# Motherboard.net
KiCad netlist of a schematic drawn in EAGLE
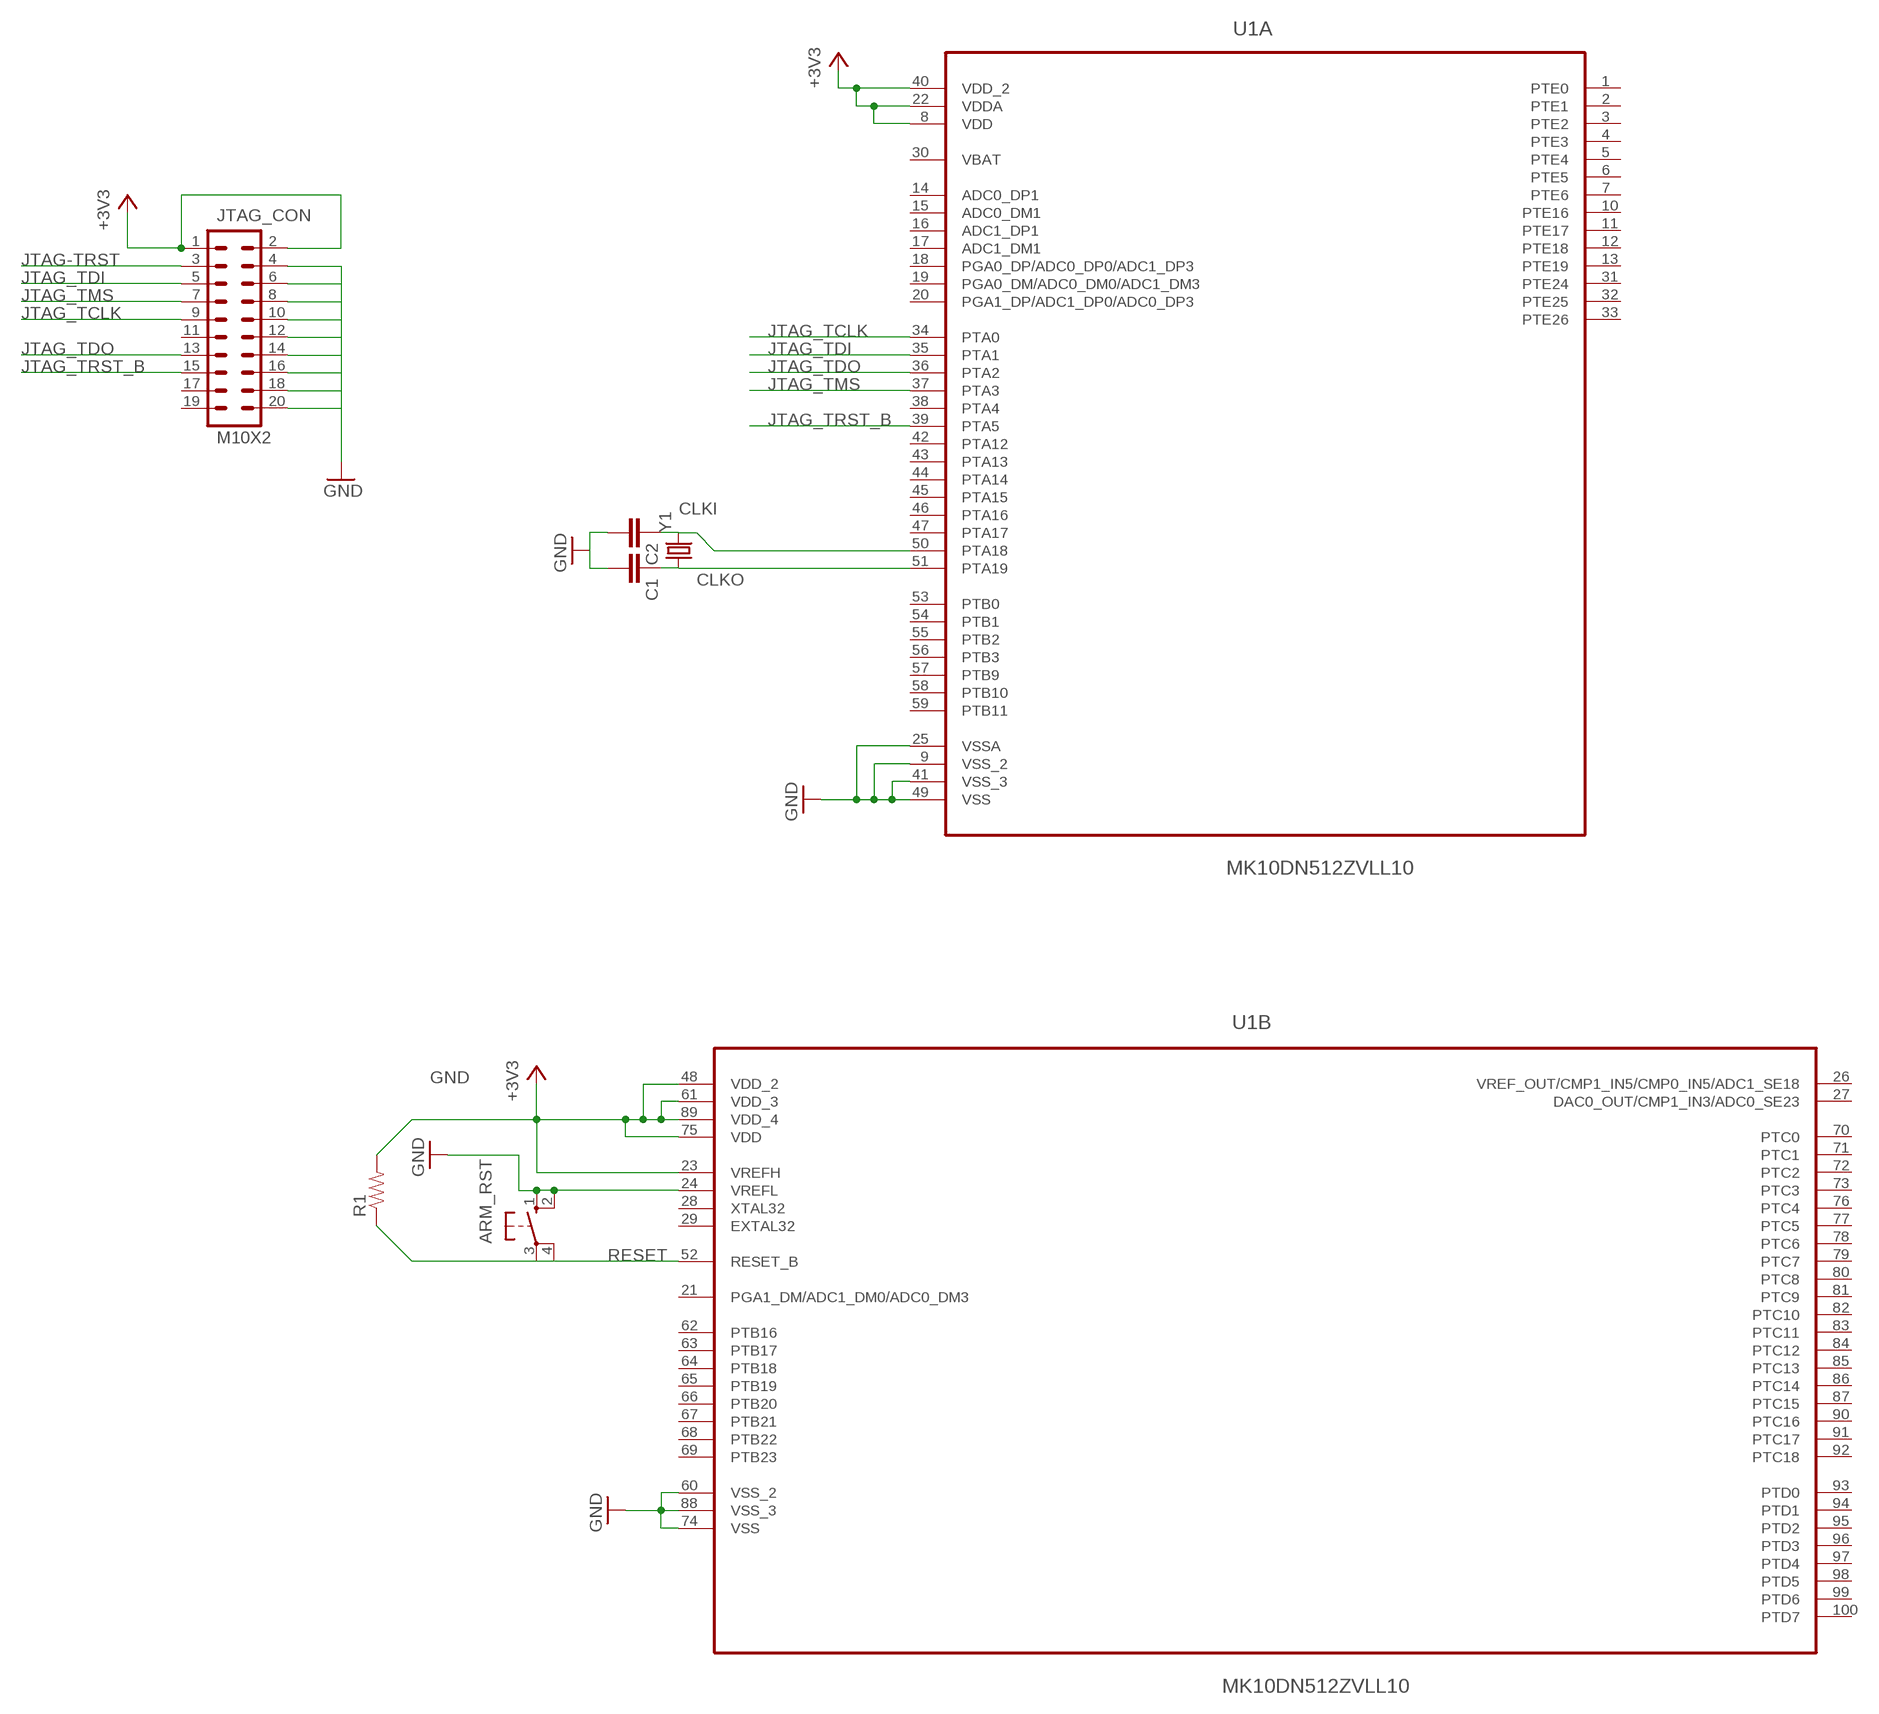
[diagram p0: schematic, sheet 1]
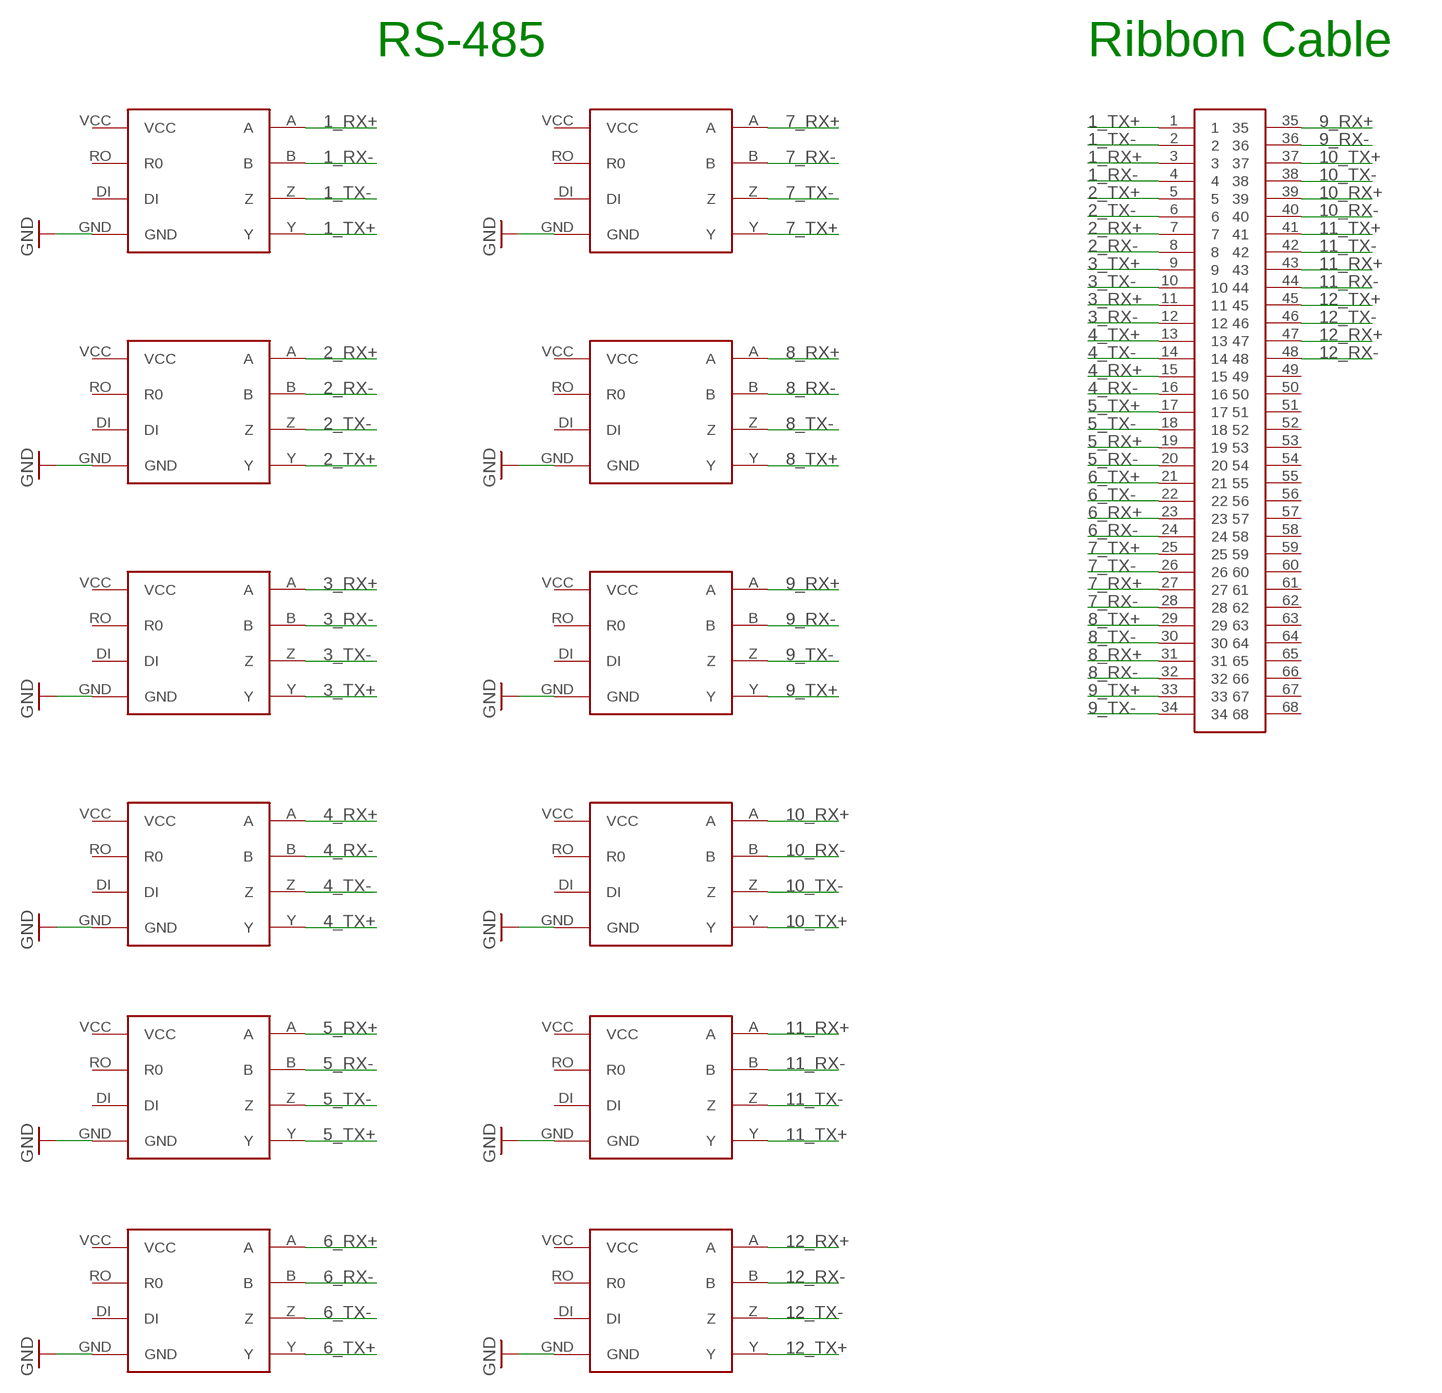
[diagram p1: schematic, sheet 2]
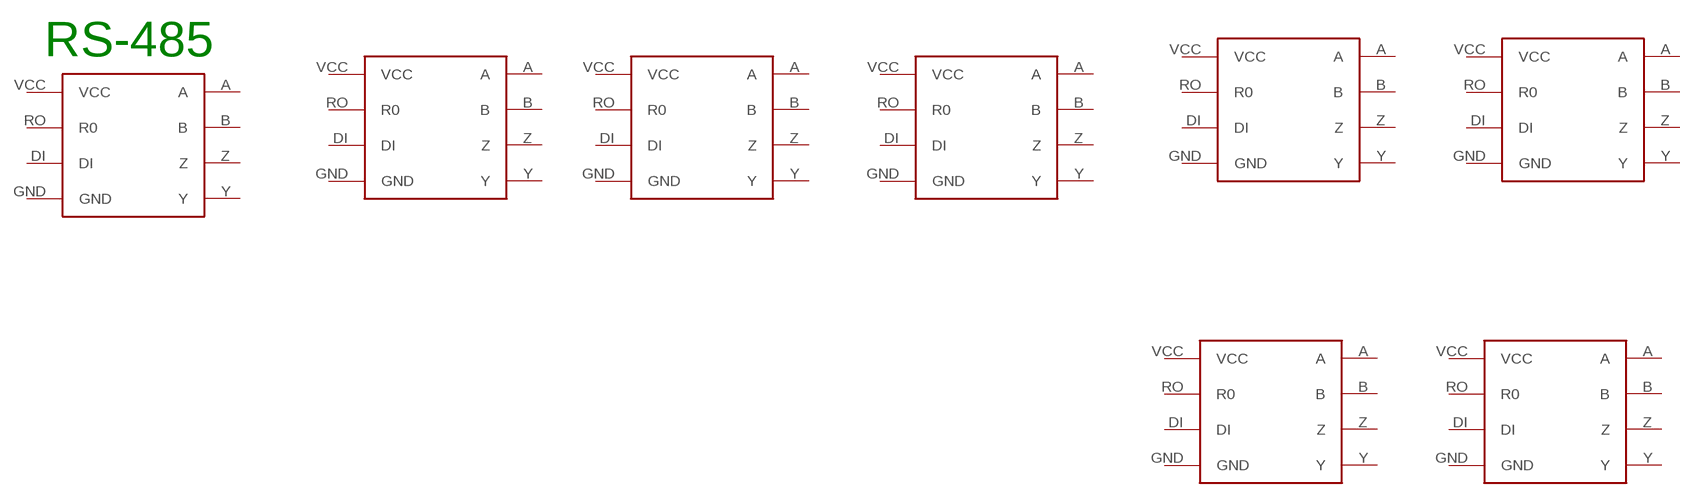
[diagram p2: schematic, sheet 3]
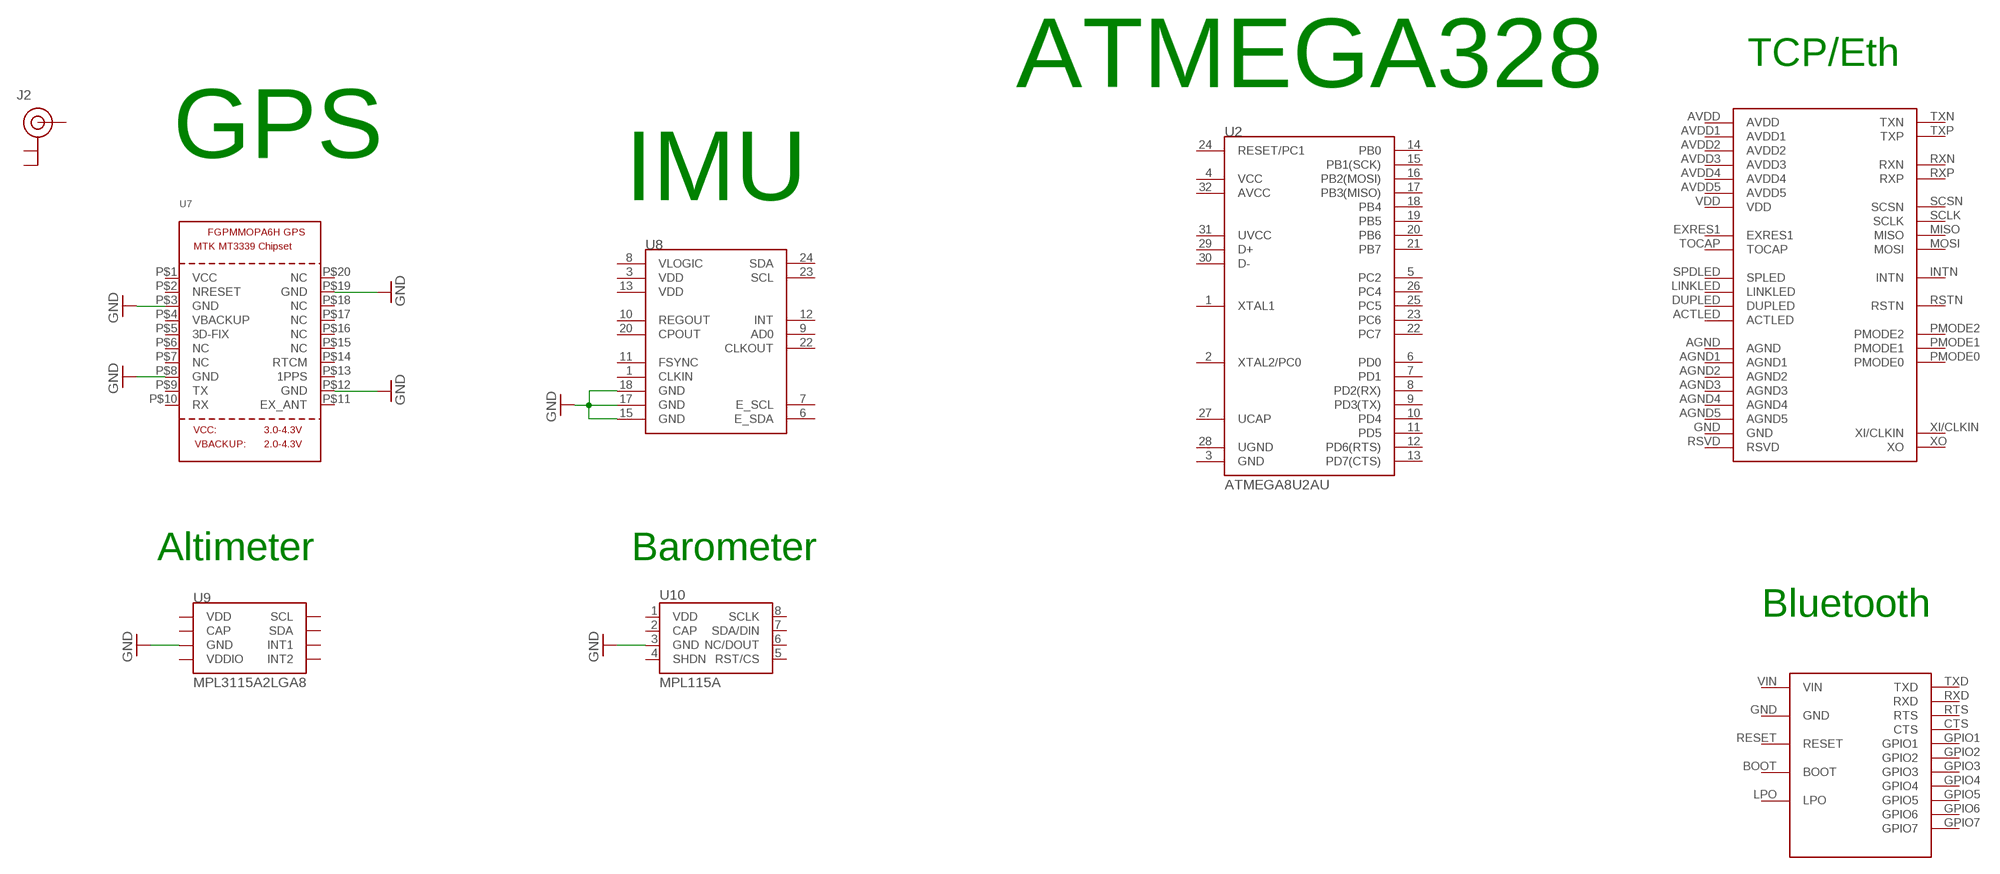
[diagram p3: schematic, sheet 4]

(export (version "E")
  (design (tool "Eeschema 10.0.6"))
  (components
    (comp (ref "ARM_RST")
      (value "10-XX")
      (footprint "eagle-import:B3F-10XX")
      (fields (field (name "MPN") "B3F-1000"))
      (libsource (lib "eagle-import") (part "10-XX"))
    )
    (comp (ref "C1")
      (value "CAPPTH1")
      (footprint "eagle-import:CAP-PTH-5MM")
      (libsource (lib "eagle-import") (part "CAPPTH1"))
    )
    (comp (ref "C2")
      (value "CAPPTH1")
      (footprint "eagle-import:CAP-PTH-5MM")
      (libsource (lib "eagle-import") (part "CAPPTH1"))
    )
    (comp (ref "JTAG_CON")
      (value "M10X2")
      (footprint "eagle-import:2X10")
      (libsource (lib "eagle-import") (part "M10X2"))
    )
    (comp (ref "R1")
      (value "RESISTORPTH-1/4W")
      (footprint "eagle-import:AXIAL-0.4")
      (libsource (lib "eagle-import") (part "RESISTORPTH-1/4W"))
    )
    (comp (ref "U1")
      (value "MK10DN512ZVLL10")
      (footprint "eagle-import:QFP50P1600X1600X170-100N")
      (libsource (lib "eagle-import") (part "MK10DN512ZVLL10"))
    )
    (comp (ref "Y1")
      (value "CRYSTALHC49US")
      (footprint "eagle-import:HC49US")
      (libsource (lib "eagle-import") (part "CRYSTALHC49US"))
    )
    (comp (ref "U$4")
      (value "MAX3077")
      (footprint "eagle-import:MAX3070E")
      (libsource (lib "eagle-import") (part "MAX3077"))
    )
    (comp (ref "U$25")
      (value "MAX3077")
      (footprint "eagle-import:MAX3070E")
      (libsource (lib "eagle-import") (part "MAX3077"))
    )
    (comp (ref "U$26")
      (value "MAX3077")
      (footprint "eagle-import:MAX3070E")
      (libsource (lib "eagle-import") (part "MAX3077"))
    )
    (comp (ref "U$27")
      (value "MAX3077")
      (footprint "eagle-import:MAX3070E")
      (libsource (lib "eagle-import") (part "MAX3077"))
    )
    (comp (ref "U$28")
      (value "MAX3077")
      (footprint "eagle-import:MAX3070E")
      (libsource (lib "eagle-import") (part "MAX3077"))
    )
    (comp (ref "U$29")
      (value "MAX3077")
      (footprint "eagle-import:MAX3070E")
      (libsource (lib "eagle-import") (part "MAX3077"))
    )
    (comp (ref "U$30")
      (value "MAX3077")
      (footprint "eagle-import:MAX3070E")
      (libsource (lib "eagle-import") (part "MAX3077"))
    )
    (comp (ref "U$31")
      (value "MAX3077")
      (footprint "eagle-import:MAX3070E")
      (libsource (lib "eagle-import") (part "MAX3077"))
    )
    (comp (ref "U$32")
      (value "MAX3077")
      (footprint "eagle-import:MAX3070E")
      (libsource (lib "eagle-import") (part "MAX3077"))
    )
    (comp (ref "U$33")
      (value "MAX3077")
      (footprint "eagle-import:MAX3070E")
      (libsource (lib "eagle-import") (part "MAX3077"))
    )
    (comp (ref "U$34")
      (value "MAX3077")
      (footprint "eagle-import:MAX3070E")
      (libsource (lib "eagle-import") (part "MAX3077"))
    )
    (comp (ref "U$35")
      (value "MAX3077")
      (footprint "eagle-import:MAX3070E")
      (libsource (lib "eagle-import") (part "MAX3077"))
    )
    (comp (ref "U$36")
      (value "TB60050685100")
      (footprint "eagle-import:60050685100")
      (libsource (lib "eagle-import") (part "TB60050685100"))
    )
    (comp (ref "U$3")
      (value "MAX3077")
      (footprint "eagle-import:MAX3070E")
      (libsource (lib "eagle-import") (part "MAX3077"))
    )
    (comp (ref "U$5")
      (value "MAX3077")
      (footprint "eagle-import:MAX3070E")
      (libsource (lib "eagle-import") (part "MAX3077"))
    )
    (comp (ref "U$6")
      (value "MAX3077")
      (footprint "eagle-import:MAX3070E")
      (libsource (lib "eagle-import") (part "MAX3077"))
    )
    (comp (ref "U$7")
      (value "MAX3077")
      (footprint "eagle-import:MAX3070E")
      (libsource (lib "eagle-import") (part "MAX3077"))
    )
    (comp (ref "U$8")
      (value "MAX3077")
      (footprint "eagle-import:MAX3070E")
      (libsource (lib "eagle-import") (part "MAX3077"))
    )
    (comp (ref "U$9")
      (value "MAX3077")
      (footprint "eagle-import:MAX3070E")
      (libsource (lib "eagle-import") (part "MAX3077"))
    )
    (comp (ref "U$10")
      (value "MAX3077")
      (footprint "eagle-import:MAX3070E")
      (libsource (lib "eagle-import") (part "MAX3077"))
    )
    (comp (ref "U$11")
      (value "MAX3077")
      (footprint "eagle-import:MAX3070E")
      (libsource (lib "eagle-import") (part "MAX3077"))
    )
    (comp (ref "J2")
      (value "U.FL")
      (footprint "eagle-import:U.FL")
      (libsource (lib "eagle-import") (part "U.FL"))
    )
    (comp (ref "U$12")
      (value "W5500")
      (footprint "eagle-import:W5500")
      (libsource (lib "eagle-import") (part "W5500"))
    )
    (comp (ref "U$13")
      (value "SPBT2632C2A")
      (footprint "eagle-import:SPBT2632C2A")
      (libsource (lib "eagle-import") (part "SPBT2632C2A"))
    )
    (comp (ref "U2")
      (value "ATMEGA8U2AU")
      (footprint "eagle-import:TQFP32-08")
      (libsource (lib "eagle-import") (part "ATMEGA8U2AU"))
    )
    (comp (ref "U7")
      (value "GPS_FGPMMOPA6H")
      (footprint "eagle-import:FGPMMOPA6H")
      (libsource (lib "eagle-import") (part "GPS_FGPMMOPA6H"))
    )
    (comp (ref "U8")
      (value "MPU-9150QFN-24-NP")
      (footprint "eagle-import:QFN-24-NP")
      (libsource (lib "eagle-import") (part "MPU-9150QFN-24-NP"))
    )
    (comp (ref "U9")
      (value "MPL3115A2LGA8")
      (footprint "eagle-import:LGA8")
      (libsource (lib "eagle-import") (part "MPL3115A2LGA8"))
    )
    (comp (ref "U10")
      (value "MPL115A")
      (footprint "eagle-import:LGA8")
      (libsource (lib "eagle-import") (part "MPL115A"))
    )
  )
  (nets
    (net (code "1") (name "+3V3") (class "Default")
      (node (ref "JTAG_CON") (pin "1") (pinfunction "1_1") (pintype "passive"))
      (node (ref "JTAG_CON") (pin "2") (pinfunction "2_2") (pintype "passive"))
      (node (ref "R1") (pin "P$2") (pinfunction "2_P$2") (pintype "passive"))
      (node (ref "U1") (pin "22") (pinfunction "VDDA_22") (pintype "power_in"))
      (node (ref "U1") (pin "23") (pinfunction "VREFH_23") (pintype "passive"))
      (node (ref "U1") (pin "40") (pinfunction "VDD_2_40") (pintype "power_in"))
      (node (ref "U1") (pin "48") (pinfunction "VDD_2_48") (pintype "power_in"))
      (node (ref "U1") (pin "61") (pinfunction "VDD_3_61") (pintype "power_in"))
      (node (ref "U1") (pin "75") (pinfunction "VDD_75") (pintype "power_in"))
      (node (ref "U1") (pin "8") (pinfunction "VDD_8") (pintype "power_in"))
      (node (ref "U1") (pin "89") (pinfunction "VDD_4_89") (pintype "power_in"))
    )
    (net (code "2") (name "1_RX+") (class "Default")
      (node (ref "U$29") (pin "A") (pinfunction "A_A") (pintype "bidirectional"))
      (node (ref "U$36") (pin "3") (pinfunction "3_3") (pintype "bidirectional"))
    )
    (net (code "3") (name "1_RX-") (class "Default")
      (node (ref "U$29") (pin "B") (pinfunction "B_B") (pintype "bidirectional"))
      (node (ref "U$36") (pin "4") (pinfunction "4_4") (pintype "bidirectional"))
    )
    (net (code "4") (name "1_TX+") (class "Default")
      (node (ref "U$29") (pin "Y") (pinfunction "Y_Y") (pintype "bidirectional"))
      (node (ref "U$36") (pin "1") (pinfunction "1_1") (pintype "bidirectional"))
    )
    (net (code "5") (name "1_TX-") (class "Default")
      (node (ref "U$29") (pin "Z") (pinfunction "Z_Z") (pintype "bidirectional"))
      (node (ref "U$36") (pin "2") (pinfunction "2_2") (pintype "bidirectional"))
    )
    (net (code "6") (name "2_RX+") (class "Default")
      (node (ref "U$31") (pin "A") (pinfunction "A_A") (pintype "bidirectional"))
      (node (ref "U$36") (pin "7") (pinfunction "7_7") (pintype "bidirectional"))
    )
    (net (code "7") (name "2_RX-") (class "Default")
      (node (ref "U$31") (pin "B") (pinfunction "B_B") (pintype "bidirectional"))
      (node (ref "U$36") (pin "8") (pinfunction "8_8") (pintype "bidirectional"))
    )
    (net (code "8") (name "2_TX+") (class "Default")
      (node (ref "U$31") (pin "Y") (pinfunction "Y_Y") (pintype "bidirectional"))
      (node (ref "U$36") (pin "5") (pinfunction "5_5") (pintype "bidirectional"))
    )
    (net (code "9") (name "2_TX-") (class "Default")
      (node (ref "U$31") (pin "Z") (pinfunction "Z_Z") (pintype "bidirectional"))
      (node (ref "U$36") (pin "6") (pinfunction "6_6") (pintype "bidirectional"))
    )
    (net (code "10") (name "3_RX+") (class "Default")
      (node (ref "U$32") (pin "A") (pinfunction "A_A") (pintype "bidirectional"))
      (node (ref "U$36") (pin "11") (pinfunction "11_11") (pintype "bidirectional"))
    )
    (net (code "11") (name "3_RX-") (class "Default")
      (node (ref "U$32") (pin "B") (pinfunction "B_B") (pintype "bidirectional"))
      (node (ref "U$36") (pin "12") (pinfunction "12_12") (pintype "bidirectional"))
    )
    (net (code "12") (name "3_TX+") (class "Default")
      (node (ref "U$32") (pin "Y") (pinfunction "Y_Y") (pintype "bidirectional"))
      (node (ref "U$36") (pin "9") (pinfunction "9_9") (pintype "bidirectional"))
    )
    (net (code "13") (name "3_TX-") (class "Default")
      (node (ref "U$32") (pin "Z") (pinfunction "Z_Z") (pintype "bidirectional"))
      (node (ref "U$36") (pin "10") (pinfunction "10_10") (pintype "bidirectional"))
    )
    (net (code "14") (name "4_RX+") (class "Default")
      (node (ref "U$33") (pin "A") (pinfunction "A_A") (pintype "bidirectional"))
      (node (ref "U$36") (pin "15") (pinfunction "15_15") (pintype "bidirectional"))
    )
    (net (code "15") (name "4_RX-") (class "Default")
      (node (ref "U$33") (pin "B") (pinfunction "B_B") (pintype "bidirectional"))
      (node (ref "U$36") (pin "16") (pinfunction "16_16") (pintype "bidirectional"))
    )
    (net (code "16") (name "4_TX+") (class "Default")
      (node (ref "U$33") (pin "Y") (pinfunction "Y_Y") (pintype "bidirectional"))
      (node (ref "U$36") (pin "13") (pinfunction "13_13") (pintype "bidirectional"))
    )
    (net (code "17") (name "4_TX-") (class "Default")
      (node (ref "U$33") (pin "Z") (pinfunction "Z_Z") (pintype "bidirectional"))
      (node (ref "U$36") (pin "14") (pinfunction "14_14") (pintype "bidirectional"))
    )
    (net (code "18") (name "5_RX+") (class "Default")
      (node (ref "U$34") (pin "A") (pinfunction "A_A") (pintype "bidirectional"))
      (node (ref "U$36") (pin "19") (pinfunction "19_19") (pintype "bidirectional"))
    )
    (net (code "19") (name "5_RX-") (class "Default")
      (node (ref "U$34") (pin "B") (pinfunction "B_B") (pintype "bidirectional"))
      (node (ref "U$36") (pin "20") (pinfunction "20_20") (pintype "bidirectional"))
    )
    (net (code "20") (name "5_TX+") (class "Default")
      (node (ref "U$34") (pin "Y") (pinfunction "Y_Y") (pintype "bidirectional"))
      (node (ref "U$36") (pin "17") (pinfunction "17_17") (pintype "bidirectional"))
    )
    (net (code "21") (name "5_TX-") (class "Default")
      (node (ref "U$34") (pin "Z") (pinfunction "Z_Z") (pintype "bidirectional"))
      (node (ref "U$36") (pin "18") (pinfunction "18_18") (pintype "bidirectional"))
    )
    (net (code "22") (name "6_RX+") (class "Default")
      (node (ref "U$35") (pin "A") (pinfunction "A_A") (pintype "bidirectional"))
      (node (ref "U$36") (pin "23") (pinfunction "23_23") (pintype "bidirectional"))
    )
    (net (code "23") (name "6_RX-") (class "Default")
      (node (ref "U$35") (pin "B") (pinfunction "B_B") (pintype "bidirectional"))
      (node (ref "U$36") (pin "24") (pinfunction "24_24") (pintype "bidirectional"))
    )
    (net (code "24") (name "6_TX+") (class "Default")
      (node (ref "U$35") (pin "Y") (pinfunction "Y_Y") (pintype "bidirectional"))
      (node (ref "U$36") (pin "21") (pinfunction "21_21") (pintype "bidirectional"))
    )
    (net (code "25") (name "6_TX-") (class "Default")
      (node (ref "U$35") (pin "Z") (pinfunction "Z_Z") (pintype "bidirectional"))
      (node (ref "U$36") (pin "22") (pinfunction "22_22") (pintype "bidirectional"))
    )
    (net (code "26") (name "7_RX+") (class "Default")
      (node (ref "U$30") (pin "A") (pinfunction "A_A") (pintype "bidirectional"))
      (node (ref "U$36") (pin "27") (pinfunction "27_27") (pintype "bidirectional"))
    )
    (net (code "27") (name "7_RX-") (class "Default")
      (node (ref "U$30") (pin "B") (pinfunction "B_B") (pintype "bidirectional"))
      (node (ref "U$36") (pin "28") (pinfunction "28_28") (pintype "bidirectional"))
    )
    (net (code "28") (name "7_TX+") (class "Default")
      (node (ref "U$30") (pin "Y") (pinfunction "Y_Y") (pintype "bidirectional"))
      (node (ref "U$36") (pin "25") (pinfunction "25_25") (pintype "bidirectional"))
    )
    (net (code "29") (name "7_TX-") (class "Default")
      (node (ref "U$30") (pin "Z") (pinfunction "Z_Z") (pintype "bidirectional"))
      (node (ref "U$36") (pin "26") (pinfunction "26_26") (pintype "bidirectional"))
    )
    (net (code "30") (name "8_RX+") (class "Default")
      (node (ref "U$28") (pin "A") (pinfunction "A_A") (pintype "bidirectional"))
      (node (ref "U$36") (pin "31") (pinfunction "31_31") (pintype "bidirectional"))
    )
    (net (code "31") (name "8_RX-") (class "Default")
      (node (ref "U$28") (pin "B") (pinfunction "B_B") (pintype "bidirectional"))
      (node (ref "U$36") (pin "32") (pinfunction "32_32") (pintype "bidirectional"))
    )
    (net (code "32") (name "8_TX+") (class "Default")
      (node (ref "U$28") (pin "Y") (pinfunction "Y_Y") (pintype "bidirectional"))
      (node (ref "U$36") (pin "29") (pinfunction "29_29") (pintype "bidirectional"))
    )
    (net (code "33") (name "8_TX-") (class "Default")
      (node (ref "U$28") (pin "Z") (pinfunction "Z_Z") (pintype "bidirectional"))
      (node (ref "U$36") (pin "30") (pinfunction "30_30") (pintype "bidirectional"))
    )
    (net (code "34") (name "9_RX+") (class "Default")
      (node (ref "U$27") (pin "A") (pinfunction "A_A") (pintype "bidirectional"))
      (node (ref "U$36") (pin "35") (pinfunction "35_35") (pintype "bidirectional"))
    )
    (net (code "35") (name "9_RX-") (class "Default")
      (node (ref "U$27") (pin "B") (pinfunction "B_B") (pintype "bidirectional"))
      (node (ref "U$36") (pin "36") (pinfunction "36_36") (pintype "bidirectional"))
    )
    (net (code "36") (name "9_TX+") (class "Default")
      (node (ref "U$27") (pin "Y") (pinfunction "Y_Y") (pintype "bidirectional"))
      (node (ref "U$36") (pin "33") (pinfunction "33_33") (pintype "bidirectional"))
    )
    (net (code "37") (name "9_TX-") (class "Default")
      (node (ref "U$27") (pin "Z") (pinfunction "Z_Z") (pintype "bidirectional"))
      (node (ref "U$36") (pin "34") (pinfunction "34_34") (pintype "bidirectional"))
    )
    (net (code "38") (name "10_RX+") (class "Default")
      (node (ref "U$26") (pin "A") (pinfunction "A_A") (pintype "bidirectional"))
      (node (ref "U$36") (pin "39") (pinfunction "39_39") (pintype "bidirectional"))
    )
    (net (code "39") (name "10_RX-") (class "Default")
      (node (ref "U$26") (pin "B") (pinfunction "B_B") (pintype "bidirectional"))
      (node (ref "U$36") (pin "40") (pinfunction "40_40") (pintype "bidirectional"))
    )
    (net (code "40") (name "10_TX+") (class "Default")
      (node (ref "U$26") (pin "Y") (pinfunction "Y_Y") (pintype "bidirectional"))
      (node (ref "U$36") (pin "37") (pinfunction "37_37") (pintype "bidirectional"))
    )
    (net (code "41") (name "10_TX-") (class "Default")
      (node (ref "U$26") (pin "Z") (pinfunction "Z_Z") (pintype "bidirectional"))
      (node (ref "U$36") (pin "38") (pinfunction "38_38") (pintype "bidirectional"))
    )
    (net (code "42") (name "11_RX+") (class "Default")
      (node (ref "U$25") (pin "A") (pinfunction "A_A") (pintype "bidirectional"))
      (node (ref "U$36") (pin "43") (pinfunction "43_43") (pintype "bidirectional"))
    )
    (net (code "43") (name "11_RX-") (class "Default")
      (node (ref "U$25") (pin "B") (pinfunction "B_B") (pintype "bidirectional"))
      (node (ref "U$36") (pin "44") (pinfunction "44_44") (pintype "bidirectional"))
    )
    (net (code "44") (name "11_TX+") (class "Default")
      (node (ref "U$25") (pin "Y") (pinfunction "Y_Y") (pintype "bidirectional"))
      (node (ref "U$36") (pin "41") (pinfunction "41_41") (pintype "bidirectional"))
    )
    (net (code "45") (name "11_TX-") (class "Default")
      (node (ref "U$25") (pin "Z") (pinfunction "Z_Z") (pintype "bidirectional"))
      (node (ref "U$36") (pin "42") (pinfunction "42_42") (pintype "bidirectional"))
    )
    (net (code "46") (name "12_RX+") (class "Default")
      (node (ref "U$36") (pin "47") (pinfunction "47_47") (pintype "bidirectional"))
      (node (ref "U$4") (pin "A") (pinfunction "A_A") (pintype "bidirectional"))
    )
    (net (code "47") (name "12_RX-") (class "Default")
      (node (ref "U$36") (pin "48") (pinfunction "48_48") (pintype "bidirectional"))
      (node (ref "U$4") (pin "B") (pinfunction "B_B") (pintype "bidirectional"))
    )
    (net (code "48") (name "12_TX+") (class "Default")
      (node (ref "U$36") (pin "45") (pinfunction "45_45") (pintype "bidirectional"))
      (node (ref "U$4") (pin "Y") (pinfunction "Y_Y") (pintype "bidirectional"))
    )
    (net (code "49") (name "12_TX-") (class "Default")
      (node (ref "U$36") (pin "46") (pinfunction "46_46") (pintype "bidirectional"))
      (node (ref "U$4") (pin "Z") (pinfunction "Z_Z") (pintype "bidirectional"))
    )
    (net (code "50") (name "CAP") (class "Default")
      (node (ref "U9") (pin "2") (pinfunction "CAP_2") (pintype "power_in"))
    )
    (net (code "51") (name "CLKI") (class "Default")
      (node (ref "C2") (pin "1") (pinfunction "1_1") (pintype "passive"))
      (node (ref "U1") (pin "50") (pinfunction "PTA18_50") (pintype "bidirectional"))
      (node (ref "Y1") (pin "2") (pinfunction "2_2") (pintype "passive"))
    )
    (net (code "52") (name "CLKO") (class "Default")
      (node (ref "C1") (pin "1") (pinfunction "1_1") (pintype "passive"))
      (node (ref "U1") (pin "51") (pinfunction "PTA19_51") (pintype "bidirectional"))
      (node (ref "Y1") (pin "1") (pinfunction "1_1") (pintype "passive"))
    )
    (net (code "53") (name "GND") (class "Default")
      (node (ref "ARM_RST") (pin "1") (pinfunction "S_1") (pintype "passive"))
      (node (ref "ARM_RST") (pin "2") (pinfunction "S1_2") (pintype "passive"))
      (node (ref "C1") (pin "2") (pinfunction "2_2") (pintype "passive"))
      (node (ref "C2") (pin "2") (pinfunction "2_2") (pintype "passive"))
      (node (ref "JTAG_CON") (pin "10") (pinfunction "10_10") (pintype "passive"))
      (node (ref "JTAG_CON") (pin "12") (pinfunction "12_12") (pintype "passive"))
      (node (ref "JTAG_CON") (pin "14") (pinfunction "14_14") (pintype "passive"))
      (node (ref "JTAG_CON") (pin "16") (pinfunction "16_16") (pintype "passive"))
      (node (ref "JTAG_CON") (pin "18") (pinfunction "18_18") (pintype "passive"))
      (node (ref "JTAG_CON") (pin "20") (pinfunction "20_20") (pintype "passive"))
      (node (ref "JTAG_CON") (pin "4") (pinfunction "4_4") (pintype "passive"))
      (node (ref "JTAG_CON") (pin "6") (pinfunction "6_6") (pintype "passive"))
      (node (ref "JTAG_CON") (pin "8") (pinfunction "8_8") (pintype "passive"))
      (node (ref "U$25") (pin "GND") (pinfunction "GND_GND") (pintype "bidirectional"))
      (node (ref "U$26") (pin "GND") (pinfunction "GND_GND") (pintype "bidirectional"))
      (node (ref "U$27") (pin "GND") (pinfunction "GND_GND") (pintype "bidirectional"))
      (node (ref "U$28") (pin "GND") (pinfunction "GND_GND") (pintype "bidirectional"))
      (node (ref "U$29") (pin "GND") (pinfunction "GND_GND") (pintype "bidirectional"))
      (node (ref "U$30") (pin "GND") (pinfunction "GND_GND") (pintype "bidirectional"))
      (node (ref "U$31") (pin "GND") (pinfunction "GND_GND") (pintype "bidirectional"))
      (node (ref "U$32") (pin "GND") (pinfunction "GND_GND") (pintype "bidirectional"))
      (node (ref "U$33") (pin "GND") (pinfunction "GND_GND") (pintype "bidirectional"))
      (node (ref "U$34") (pin "GND") (pinfunction "GND_GND") (pintype "bidirectional"))
      (node (ref "U$35") (pin "GND") (pinfunction "GND_GND") (pintype "bidirectional"))
      (node (ref "U$4") (pin "GND") (pinfunction "GND_GND") (pintype "bidirectional"))
      (node (ref "U1") (pin "24") (pinfunction "VREFL_24") (pintype "passive"))
      (node (ref "U1") (pin "25") (pinfunction "VSSA_25") (pintype "passive"))
      (node (ref "U1") (pin "41") (pinfunction "VSS_3_41") (pintype "passive"))
      (node (ref "U1") (pin "49") (pinfunction "VSS_49") (pintype "passive"))
      (node (ref "U1") (pin "60") (pinfunction "VSS_2_60") (pintype "passive"))
      (node (ref "U1") (pin "74") (pinfunction "VSS_74") (pintype "passive"))
      (node (ref "U1") (pin "88") (pinfunction "VSS_3_88") (pintype "passive"))
      (node (ref "U1") (pin "9") (pinfunction "VSS_2_9") (pintype "passive"))
      (node (ref "U10") (pin "3") (pinfunction "GND_3") (pintype "bidirectional"))
      (node (ref "U7") (pin "P$12") (pinfunction "GND_P$12") (pintype "bidirectional"))
      (node (ref "U7") (pin "P$19") (pinfunction "GND_P$19") (pintype "bidirectional"))
      (node (ref "U7") (pin "P$3") (pinfunction "GND_P$3") (pintype "bidirectional"))
      (node (ref "U7") (pin "P$8") (pinfunction "GND_P$8") (pintype "bidirectional"))
      (node (ref "U8") (pin "15") (pinfunction "GND_15") (pintype "bidirectional"))
      (node (ref "U8") (pin "17") (pinfunction "GND_17") (pintype "bidirectional"))
      (node (ref "U8") (pin "18") (pinfunction "GND_18") (pintype "bidirectional"))
      (node (ref "U9") (pin "3") (pinfunction "GND_3") (pintype "power_in"))
    )
    (net (code "54") (name "JTAG-TRST") (class "Default")
      (node (ref "JTAG_CON") (pin "3") (pinfunction "3_3") (pintype "passive"))
    )
    (net (code "55") (name "JTAG_TCLK") (class "Default")
      (node (ref "JTAG_CON") (pin "9") (pinfunction "9_9") (pintype "passive"))
      (node (ref "U1") (pin "34") (pinfunction "PTA0_34") (pintype "bidirectional"))
    )
    (net (code "56") (name "JTAG_TDI") (class "Default")
      (node (ref "JTAG_CON") (pin "5") (pinfunction "5_5") (pintype "passive"))
      (node (ref "U1") (pin "35") (pinfunction "PTA1_35") (pintype "bidirectional"))
    )
    (net (code "57") (name "JTAG_TDO") (class "Default")
      (node (ref "JTAG_CON") (pin "13") (pinfunction "13_13") (pintype "passive"))
      (node (ref "U1") (pin "36") (pinfunction "PTA2_36") (pintype "bidirectional"))
    )
    (net (code "58") (name "JTAG_TMS") (class "Default")
      (node (ref "JTAG_CON") (pin "7") (pinfunction "7_7") (pintype "passive"))
      (node (ref "U1") (pin "37") (pinfunction "PTA3_37") (pintype "bidirectional"))
    )
    (net (code "59") (name "JTAG_TRST_B") (class "Default")
      (node (ref "JTAG_CON") (pin "15") (pinfunction "15_15") (pintype "passive"))
      (node (ref "U1") (pin "39") (pinfunction "PTA5_39") (pintype "bidirectional"))
    )
    (net (code "60") (name "RESET") (class "Default")
      (node (ref "ARM_RST") (pin "3") (pinfunction "P_3") (pintype "passive"))
      (node (ref "ARM_RST") (pin "4") (pinfunction "P1_4") (pintype "passive"))
      (node (ref "R1") (pin "P$1") (pinfunction "1_P$1") (pintype "passive"))
      (node (ref "U1") (pin "52") (pinfunction "RESET_B_52") (pintype "passive"))
    )
    (net (code "61") (name "VBAT") (class "Default")
      (node (ref "U1") (pin "30") (pinfunction "VBAT_30") (pintype "power_in"))
    )
    (net (code "62") (name "VDD") (class "Default")
      (node (ref "U9") (pin "1") (pinfunction "VDD_1") (pintype "power_in"))
    )
    (net (code "63") (name "VDDIO") (class "Default")
      (node (ref "U9") (pin "4") (pinfunction "VDDIO_4") (pintype "power_in"))
    )
    (net (code "64") (name "unconnected-(J2-GND-PadP$1)") (class "Default")
      (node (ref "J2") (pin "P$1") (pinfunction "GND_P$1") (pintype "bidirectional"))
    )
    (net (code "65") (name "unconnected-(J2-GND-PadP$2)") (class "Default")
      (node (ref "J2") (pin "P$2") (pinfunction "GND_P$2") (pintype "bidirectional"))
    )
    (net (code "66") (name "unconnected-(J2-SIGNAL-PadP$3)") (class "Default")
      (node (ref "J2") (pin "P$3") (pinfunction "SIGNAL_P$3") (pintype "bidirectional"))
    )
    (net (code "67") (name "unconnected-(JTAG_CON-Pad11)") (class "Default")
      (node (ref "JTAG_CON") (pin "11") (pinfunction "11_11") (pintype "passive"))
    )
    (net (code "68") (name "unconnected-(JTAG_CON-Pad17)") (class "Default")
      (node (ref "JTAG_CON") (pin "17") (pinfunction "17_17") (pintype "passive"))
    )
    (net (code "69") (name "unconnected-(JTAG_CON-Pad19)") (class "Default")
      (node (ref "JTAG_CON") (pin "19") (pinfunction "19_19") (pintype "passive"))
    )
    (net (code "70") (name "unconnected-(U$3-PadA)") (class "Default")
      (node (ref "U$3") (pin "A") (pinfunction "A_A") (pintype "bidirectional"))
    )
    (net (code "71") (name "unconnected-(U$3-PadB)") (class "Default")
      (node (ref "U$3") (pin "B") (pinfunction "B_B") (pintype "bidirectional"))
    )
    (net (code "72") (name "unconnected-(U$3-PadDI)") (class "Default")
      (node (ref "U$3") (pin "DI") (pinfunction "DI_DI") (pintype "bidirectional"))
    )
    (net (code "73") (name "unconnected-(U$3-PadGND)") (class "Default")
      (node (ref "U$3") (pin "GND") (pinfunction "GND_GND") (pintype "bidirectional"))
    )
    (net (code "74") (name "unconnected-(U$3-PadVCC)") (class "Default")
      (node (ref "U$3") (pin "VCC") (pinfunction "VCC_VCC") (pintype "bidirectional"))
    )
    (net (code "75") (name "unconnected-(U$3-PadY)") (class "Default")
      (node (ref "U$3") (pin "Y") (pinfunction "Y_Y") (pintype "bidirectional"))
    )
    (net (code "76") (name "unconnected-(U$3-PadZ)") (class "Default")
      (node (ref "U$3") (pin "Z") (pinfunction "Z_Z") (pintype "bidirectional"))
    )
    (net (code "77") (name "unconnected-(U$3-R0-PadRO)") (class "Default")
      (node (ref "U$3") (pin "RO") (pinfunction "R0_RO") (pintype "bidirectional"))
    )
    (net (code "78") (name "unconnected-(U$4-PadDI)") (class "Default")
      (node (ref "U$4") (pin "DI") (pinfunction "DI_DI") (pintype "bidirectional"))
    )
    (net (code "79") (name "unconnected-(U$4-PadVCC)") (class "Default")
      (node (ref "U$4") (pin "VCC") (pinfunction "VCC_VCC") (pintype "bidirectional"))
    )
    (net (code "80") (name "unconnected-(U$4-R0-PadRO)") (class "Default")
      (node (ref "U$4") (pin "RO") (pinfunction "R0_RO") (pintype "bidirectional"))
    )
    (net (code "81") (name "unconnected-(U$5-PadA)") (class "Default")
      (node (ref "U$5") (pin "A") (pinfunction "A_A") (pintype "bidirectional"))
    )
    (net (code "82") (name "unconnected-(U$5-PadB)") (class "Default")
      (node (ref "U$5") (pin "B") (pinfunction "B_B") (pintype "bidirectional"))
    )
    (net (code "83") (name "unconnected-(U$5-PadDI)") (class "Default")
      (node (ref "U$5") (pin "DI") (pinfunction "DI_DI") (pintype "bidirectional"))
    )
    (net (code "84") (name "unconnected-(U$5-PadGND)") (class "Default")
      (node (ref "U$5") (pin "GND") (pinfunction "GND_GND") (pintype "bidirectional"))
    )
    (net (code "85") (name "unconnected-(U$5-PadVCC)") (class "Default")
      (node (ref "U$5") (pin "VCC") (pinfunction "VCC_VCC") (pintype "bidirectional"))
    )
    (net (code "86") (name "unconnected-(U$5-PadY)") (class "Default")
      (node (ref "U$5") (pin "Y") (pinfunction "Y_Y") (pintype "bidirectional"))
    )
    (net (code "87") (name "unconnected-(U$5-PadZ)") (class "Default")
      (node (ref "U$5") (pin "Z") (pinfunction "Z_Z") (pintype "bidirectional"))
    )
    (net (code "88") (name "unconnected-(U$5-R0-PadRO)") (class "Default")
      (node (ref "U$5") (pin "RO") (pinfunction "R0_RO") (pintype "bidirectional"))
    )
    (net (code "89") (name "unconnected-(U$6-PadA)") (class "Default")
      (node (ref "U$6") (pin "A") (pinfunction "A_A") (pintype "bidirectional"))
    )
    (net (code "90") (name "unconnected-(U$6-PadB)") (class "Default")
      (node (ref "U$6") (pin "B") (pinfunction "B_B") (pintype "bidirectional"))
    )
    (net (code "91") (name "unconnected-(U$6-PadDI)") (class "Default")
      (node (ref "U$6") (pin "DI") (pinfunction "DI_DI") (pintype "bidirectional"))
    )
    (net (code "92") (name "unconnected-(U$6-PadGND)") (class "Default")
      (node (ref "U$6") (pin "GND") (pinfunction "GND_GND") (pintype "bidirectional"))
    )
    (net (code "93") (name "unconnected-(U$6-PadVCC)") (class "Default")
      (node (ref "U$6") (pin "VCC") (pinfunction "VCC_VCC") (pintype "bidirectional"))
    )
    (net (code "94") (name "unconnected-(U$6-PadY)") (class "Default")
      (node (ref "U$6") (pin "Y") (pinfunction "Y_Y") (pintype "bidirectional"))
    )
    (net (code "95") (name "unconnected-(U$6-PadZ)") (class "Default")
      (node (ref "U$6") (pin "Z") (pinfunction "Z_Z") (pintype "bidirectional"))
    )
    (net (code "96") (name "unconnected-(U$6-R0-PadRO)") (class "Default")
      (node (ref "U$6") (pin "RO") (pinfunction "R0_RO") (pintype "bidirectional"))
    )
    (net (code "97") (name "unconnected-(U$7-PadA)") (class "Default")
      (node (ref "U$7") (pin "A") (pinfunction "A_A") (pintype "bidirectional"))
    )
    (net (code "98") (name "unconnected-(U$7-PadB)") (class "Default")
      (node (ref "U$7") (pin "B") (pinfunction "B_B") (pintype "bidirectional"))
    )
    (net (code "99") (name "unconnected-(U$7-PadDI)") (class "Default")
      (node (ref "U$7") (pin "DI") (pinfunction "DI_DI") (pintype "bidirectional"))
    )
    (net (code "100") (name "unconnected-(U$7-PadGND)") (class "Default")
      (node (ref "U$7") (pin "GND") (pinfunction "GND_GND") (pintype "bidirectional"))
    )
    (net (code "101") (name "unconnected-(U$7-PadVCC)") (class "Default")
      (node (ref "U$7") (pin "VCC") (pinfunction "VCC_VCC") (pintype "bidirectional"))
    )
    (net (code "102") (name "unconnected-(U$7-PadY)") (class "Default")
      (node (ref "U$7") (pin "Y") (pinfunction "Y_Y") (pintype "bidirectional"))
    )
    (net (code "103") (name "unconnected-(U$7-PadZ)") (class "Default")
      (node (ref "U$7") (pin "Z") (pinfunction "Z_Z") (pintype "bidirectional"))
    )
    (net (code "104") (name "unconnected-(U$7-R0-PadRO)") (class "Default")
      (node (ref "U$7") (pin "RO") (pinfunction "R0_RO") (pintype "bidirectional"))
    )
    (net (code "105") (name "unconnected-(U$8-PadA)") (class "Default")
      (node (ref "U$8") (pin "A") (pinfunction "A_A") (pintype "bidirectional"))
    )
    (net (code "106") (name "unconnected-(U$8-PadB)") (class "Default")
      (node (ref "U$8") (pin "B") (pinfunction "B_B") (pintype "bidirectional"))
    )
    (net (code "107") (name "unconnected-(U$8-PadDI)") (class "Default")
      (node (ref "U$8") (pin "DI") (pinfunction "DI_DI") (pintype "bidirectional"))
    )
    (net (code "108") (name "unconnected-(U$8-PadGND)") (class "Default")
      (node (ref "U$8") (pin "GND") (pinfunction "GND_GND") (pintype "bidirectional"))
    )
    (net (code "109") (name "unconnected-(U$8-PadVCC)") (class "Default")
      (node (ref "U$8") (pin "VCC") (pinfunction "VCC_VCC") (pintype "bidirectional"))
    )
    (net (code "110") (name "unconnected-(U$8-PadY)") (class "Default")
      (node (ref "U$8") (pin "Y") (pinfunction "Y_Y") (pintype "bidirectional"))
    )
    (net (code "111") (name "unconnected-(U$8-PadZ)") (class "Default")
      (node (ref "U$8") (pin "Z") (pinfunction "Z_Z") (pintype "bidirectional"))
    )
    (net (code "112") (name "unconnected-(U$8-R0-PadRO)") (class "Default")
      (node (ref "U$8") (pin "RO") (pinfunction "R0_RO") (pintype "bidirectional"))
    )
    (net (code "113") (name "unconnected-(U$9-PadA)") (class "Default")
      (node (ref "U$9") (pin "A") (pinfunction "A_A") (pintype "bidirectional"))
    )
    (net (code "114") (name "unconnected-(U$9-PadB)") (class "Default")
      (node (ref "U$9") (pin "B") (pinfunction "B_B") (pintype "bidirectional"))
    )
    (net (code "115") (name "unconnected-(U$9-PadDI)") (class "Default")
      (node (ref "U$9") (pin "DI") (pinfunction "DI_DI") (pintype "bidirectional"))
    )
    (net (code "116") (name "unconnected-(U$9-PadGND)") (class "Default")
      (node (ref "U$9") (pin "GND") (pinfunction "GND_GND") (pintype "bidirectional"))
    )
    (net (code "117") (name "unconnected-(U$9-PadVCC)") (class "Default")
      (node (ref "U$9") (pin "VCC") (pinfunction "VCC_VCC") (pintype "bidirectional"))
    )
    (net (code "118") (name "unconnected-(U$9-PadY)") (class "Default")
      (node (ref "U$9") (pin "Y") (pinfunction "Y_Y") (pintype "bidirectional"))
    )
    (net (code "119") (name "unconnected-(U$9-PadZ)") (class "Default")
      (node (ref "U$9") (pin "Z") (pinfunction "Z_Z") (pintype "bidirectional"))
    )
    (net (code "120") (name "unconnected-(U$9-R0-PadRO)") (class "Default")
      (node (ref "U$9") (pin "RO") (pinfunction "R0_RO") (pintype "bidirectional"))
    )
    (net (code "121") (name "unconnected-(U$10-PadA)") (class "Default")
      (node (ref "U$10") (pin "A") (pinfunction "A_A") (pintype "bidirectional"))
    )
    (net (code "122") (name "unconnected-(U$10-PadB)") (class "Default")
      (node (ref "U$10") (pin "B") (pinfunction "B_B") (pintype "bidirectional"))
    )
    (net (code "123") (name "unconnected-(U$10-PadDI)") (class "Default")
      (node (ref "U$10") (pin "DI") (pinfunction "DI_DI") (pintype "bidirectional"))
    )
    (net (code "124") (name "unconnected-(U$10-PadGND)") (class "Default")
      (node (ref "U$10") (pin "GND") (pinfunction "GND_GND") (pintype "bidirectional"))
    )
    (net (code "125") (name "unconnected-(U$10-PadVCC)") (class "Default")
      (node (ref "U$10") (pin "VCC") (pinfunction "VCC_VCC") (pintype "bidirectional"))
    )
    (net (code "126") (name "unconnected-(U$10-PadY)") (class "Default")
      (node (ref "U$10") (pin "Y") (pinfunction "Y_Y") (pintype "bidirectional"))
    )
    (net (code "127") (name "unconnected-(U$10-PadZ)") (class "Default")
      (node (ref "U$10") (pin "Z") (pinfunction "Z_Z") (pintype "bidirectional"))
    )
    (net (code "128") (name "unconnected-(U$10-R0-PadRO)") (class "Default")
      (node (ref "U$10") (pin "RO") (pinfunction "R0_RO") (pintype "bidirectional"))
    )
    (net (code "129") (name "unconnected-(U$11-PadA)") (class "Default")
      (node (ref "U$11") (pin "A") (pinfunction "A_A") (pintype "bidirectional"))
    )
    (net (code "130") (name "unconnected-(U$11-PadB)") (class "Default")
      (node (ref "U$11") (pin "B") (pinfunction "B_B") (pintype "bidirectional"))
    )
    (net (code "131") (name "unconnected-(U$11-PadDI)") (class "Default")
      (node (ref "U$11") (pin "DI") (pinfunction "DI_DI") (pintype "bidirectional"))
    )
    (net (code "132") (name "unconnected-(U$11-PadGND)") (class "Default")
      (node (ref "U$11") (pin "GND") (pinfunction "GND_GND") (pintype "bidirectional"))
    )
    (net (code "133") (name "unconnected-(U$11-PadVCC)") (class "Default")
      (node (ref "U$11") (pin "VCC") (pinfunction "VCC_VCC") (pintype "bidirectional"))
    )
    (net (code "134") (name "unconnected-(U$11-PadY)") (class "Default")
      (node (ref "U$11") (pin "Y") (pinfunction "Y_Y") (pintype "bidirectional"))
    )
    (net (code "135") (name "unconnected-(U$11-PadZ)") (class "Default")
      (node (ref "U$11") (pin "Z") (pinfunction "Z_Z") (pintype "bidirectional"))
    )
    (net (code "136") (name "unconnected-(U$11-R0-PadRO)") (class "Default")
      (node (ref "U$11") (pin "RO") (pinfunction "R0_RO") (pintype "bidirectional"))
    )
    (net (code "137") (name "unconnected-(U$12-PadACTLED)") (class "Default")
      (node (ref "U$12") (pin "ACTLED") (pinfunction "ACTLED_ACTLED") (pintype "bidirectional"))
    )
    (net (code "138") (name "unconnected-(U$12-PadAGND)") (class "Default")
      (node (ref "U$12") (pin "AGND") (pinfunction "AGND_AGND") (pintype "bidirectional"))
    )
    (net (code "139") (name "unconnected-(U$12-PadAGND1)") (class "Default")
      (node (ref "U$12") (pin "AGND1") (pinfunction "AGND1_AGND1") (pintype "bidirectional"))
    )
    (net (code "140") (name "unconnected-(U$12-PadAGND2)") (class "Default")
      (node (ref "U$12") (pin "AGND2") (pinfunction "AGND2_AGND2") (pintype "bidirectional"))
    )
    (net (code "141") (name "unconnected-(U$12-PadAGND3)") (class "Default")
      (node (ref "U$12") (pin "AGND3") (pinfunction "AGND3_AGND3") (pintype "bidirectional"))
    )
    (net (code "142") (name "unconnected-(U$12-PadAGND4)") (class "Default")
      (node (ref "U$12") (pin "AGND4") (pinfunction "AGND4_AGND4") (pintype "bidirectional"))
    )
    (net (code "143") (name "unconnected-(U$12-PadAGND5)") (class "Default")
      (node (ref "U$12") (pin "AGND5") (pinfunction "AGND5_AGND5") (pintype "bidirectional"))
    )
    (net (code "144") (name "unconnected-(U$12-PadAVDD)") (class "Default")
      (node (ref "U$12") (pin "AVDD") (pinfunction "AVDD_AVDD") (pintype "bidirectional"))
    )
    (net (code "145") (name "unconnected-(U$12-PadAVDD1)") (class "Default")
      (node (ref "U$12") (pin "AVDD1") (pinfunction "AVDD1_AVDD1") (pintype "bidirectional"))
    )
    (net (code "146") (name "unconnected-(U$12-PadAVDD2)") (class "Default")
      (node (ref "U$12") (pin "AVDD2") (pinfunction "AVDD2_AVDD2") (pintype "bidirectional"))
    )
    (net (code "147") (name "unconnected-(U$12-PadAVDD3)") (class "Default")
      (node (ref "U$12") (pin "AVDD3") (pinfunction "AVDD3_AVDD3") (pintype "bidirectional"))
    )
    (net (code "148") (name "unconnected-(U$12-PadAVDD4)") (class "Default")
      (node (ref "U$12") (pin "AVDD4") (pinfunction "AVDD4_AVDD4") (pintype "bidirectional"))
    )
    (net (code "149") (name "unconnected-(U$12-PadAVDD5)") (class "Default")
      (node (ref "U$12") (pin "AVDD5") (pinfunction "AVDD5_AVDD5") (pintype "bidirectional"))
    )
    (net (code "150") (name "unconnected-(U$12-PadDUPLED)") (class "Default")
      (node (ref "U$12") (pin "DUPLED") (pinfunction "DUPLED_DUPLED") (pintype "bidirectional"))
    )
    (net (code "151") (name "unconnected-(U$12-PadEXRES1)") (class "Default")
      (node (ref "U$12") (pin "EXRES1") (pinfunction "EXRES1_EXRES1") (pintype "bidirectional"))
    )
    (net (code "152") (name "unconnected-(U$12-PadGND)") (class "Default")
      (node (ref "U$12") (pin "GND") (pinfunction "GND_GND") (pintype "bidirectional"))
    )
    (net (code "153") (name "unconnected-(U$12-PadINTN)") (class "Default")
      (node (ref "U$12") (pin "INTN") (pinfunction "INTN_INTN") (pintype "bidirectional"))
    )
    (net (code "154") (name "unconnected-(U$12-PadLINKLED)") (class "Default")
      (node (ref "U$12") (pin "LINKLED") (pinfunction "LINKLED_LINKLED") (pintype "bidirectional"))
    )
    (net (code "155") (name "unconnected-(U$12-PadMISO)") (class "Default")
      (node (ref "U$12") (pin "MISO") (pinfunction "MISO_MISO") (pintype "bidirectional"))
    )
    (net (code "156") (name "unconnected-(U$12-PadMOSI)") (class "Default")
      (node (ref "U$12") (pin "MOSI") (pinfunction "MOSI_MOSI") (pintype "bidirectional"))
    )
    (net (code "157") (name "unconnected-(U$12-PadPMODE0)") (class "Default")
      (node (ref "U$12") (pin "PMODE0") (pinfunction "PMODE0_PMODE0") (pintype "bidirectional"))
    )
    (net (code "158") (name "unconnected-(U$12-PadPMODE1)") (class "Default")
      (node (ref "U$12") (pin "PMODE1") (pinfunction "PMODE1_PMODE1") (pintype "bidirectional"))
    )
    (net (code "159") (name "unconnected-(U$12-PadPMODE2)") (class "Default")
      (node (ref "U$12") (pin "PMODE2") (pinfunction "PMODE2_PMODE2") (pintype "bidirectional"))
    )
    (net (code "160") (name "unconnected-(U$12-PadRSTN)") (class "Default")
      (node (ref "U$12") (pin "RSTN") (pinfunction "RSTN_RSTN") (pintype "bidirectional"))
    )
    (net (code "161") (name "unconnected-(U$12-PadRSVD)") (class "Default")
      (node (ref "U$12") (pin "RSVD") (pinfunction "RSVD_RSVD") (pintype "bidirectional"))
    )
    (net (code "162") (name "unconnected-(U$12-PadRXN)") (class "Default")
      (node (ref "U$12") (pin "RXN") (pinfunction "RXN_RXN") (pintype "bidirectional"))
    )
    (net (code "163") (name "unconnected-(U$12-PadRXP)") (class "Default")
      (node (ref "U$12") (pin "RXP") (pinfunction "RXP_RXP") (pintype "bidirectional"))
    )
    (net (code "164") (name "unconnected-(U$12-PadSCLK)") (class "Default")
      (node (ref "U$12") (pin "SCLK") (pinfunction "SCLK_SCLK") (pintype "bidirectional"))
    )
    (net (code "165") (name "unconnected-(U$12-PadSCSN)") (class "Default")
      (node (ref "U$12") (pin "SCSN") (pinfunction "SCSN_SCSN") (pintype "bidirectional"))
    )
    (net (code "166") (name "unconnected-(U$12-PadTOCAP)") (class "Default")
      (node (ref "U$12") (pin "TOCAP") (pinfunction "TOCAP_TOCAP") (pintype "bidirectional"))
    )
    (net (code "167") (name "unconnected-(U$12-PadTXN)") (class "Default")
      (node (ref "U$12") (pin "TXN") (pinfunction "TXN_TXN") (pintype "bidirectional"))
    )
    (net (code "168") (name "unconnected-(U$12-PadTXP)") (class "Default")
      (node (ref "U$12") (pin "TXP") (pinfunction "TXP_TXP") (pintype "bidirectional"))
    )
    (net (code "169") (name "unconnected-(U$12-PadVDD)") (class "Default")
      (node (ref "U$12") (pin "VDD") (pinfunction "VDD_VDD") (pintype "bidirectional"))
    )
    (net (code "170") (name "unconnected-(U$12-PadXI{slash}CLKIN)") (class "Default")
      (node (ref "U$12") (pin "XI/CLKIN") (pinfunction "XI/CLKIN_XI/CLKIN") (pintype "bidirectional"))
    )
    (net (code "171") (name "unconnected-(U$12-PadXO)") (class "Default")
      (node (ref "U$12") (pin "XO") (pinfunction "XO_XO") (pintype "bidirectional"))
    )
    (net (code "172") (name "unconnected-(U$12-SPLED-PadSPDLED)") (class "Default")
      (node (ref "U$12") (pin "SPDLED") (pinfunction "SPLED_SPDLED") (pintype "bidirectional"))
    )
    (net (code "173") (name "unconnected-(U$13-PadBOOT)") (class "Default")
      (node (ref "U$13") (pin "BOOT") (pinfunction "BOOT_BOOT") (pintype "bidirectional"))
    )
    (net (code "174") (name "unconnected-(U$13-PadCTS)") (class "Default")
      (node (ref "U$13") (pin "CTS") (pinfunction "CTS_CTS") (pintype "bidirectional"))
    )
    (net (code "175") (name "unconnected-(U$13-PadGND)") (class "Default")
      (node (ref "U$13") (pin "GND") (pinfunction "GND_GND") (pintype "bidirectional"))
    )
    (net (code "176") (name "unconnected-(U$13-PadGPIO1)") (class "Default")
      (node (ref "U$13") (pin "GPIO1") (pinfunction "GPIO1_GPIO1") (pintype "bidirectional"))
    )
    (net (code "177") (name "unconnected-(U$13-PadGPIO2)") (class "Default")
      (node (ref "U$13") (pin "GPIO2") (pinfunction "GPIO2_GPIO2") (pintype "bidirectional"))
    )
    (net (code "178") (name "unconnected-(U$13-PadGPIO3)") (class "Default")
      (node (ref "U$13") (pin "GPIO3") (pinfunction "GPIO3_GPIO3") (pintype "bidirectional"))
    )
    (net (code "179") (name "unconnected-(U$13-PadGPIO4)") (class "Default")
      (node (ref "U$13") (pin "GPIO4") (pinfunction "GPIO4_GPIO4") (pintype "bidirectional"))
    )
    (net (code "180") (name "unconnected-(U$13-PadGPIO5)") (class "Default")
      (node (ref "U$13") (pin "GPIO5") (pinfunction "GPIO5_GPIO5") (pintype "bidirectional"))
    )
    (net (code "181") (name "unconnected-(U$13-PadGPIO6)") (class "Default")
      (node (ref "U$13") (pin "GPIO6") (pinfunction "GPIO6_GPIO6") (pintype "bidirectional"))
    )
    (net (code "182") (name "unconnected-(U$13-PadGPIO7)") (class "Default")
      (node (ref "U$13") (pin "GPIO7") (pinfunction "GPIO7_GPIO7") (pintype "bidirectional"))
    )
    (net (code "183") (name "unconnected-(U$13-PadLPO)") (class "Default")
      (node (ref "U$13") (pin "LPO") (pinfunction "LPO_LPO") (pintype "bidirectional"))
    )
    (net (code "184") (name "unconnected-(U$13-PadRESET)") (class "Default")
      (node (ref "U$13") (pin "RESET") (pinfunction "RESET_RESET") (pintype "bidirectional"))
    )
    (net (code "185") (name "unconnected-(U$13-PadRTS)") (class "Default")
      (node (ref "U$13") (pin "RTS") (pinfunction "RTS_RTS") (pintype "bidirectional"))
    )
    (net (code "186") (name "unconnected-(U$13-PadRXD)") (class "Default")
      (node (ref "U$13") (pin "RXD") (pinfunction "RXD_RXD") (pintype "bidirectional"))
    )
    (net (code "187") (name "unconnected-(U$13-PadTXD)") (class "Default")
      (node (ref "U$13") (pin "TXD") (pinfunction "TXD_TXD") (pintype "bidirectional"))
    )
    (net (code "188") (name "unconnected-(U$13-PadVIN)") (class "Default")
      (node (ref "U$13") (pin "VIN") (pinfunction "VIN_VIN") (pintype "bidirectional"))
    )
    (net (code "189") (name "unconnected-(U$25-PadDI)") (class "Default")
      (node (ref "U$25") (pin "DI") (pinfunction "DI_DI") (pintype "bidirectional"))
    )
    (net (code "190") (name "unconnected-(U$25-PadVCC)") (class "Default")
      (node (ref "U$25") (pin "VCC") (pinfunction "VCC_VCC") (pintype "bidirectional"))
    )
    (net (code "191") (name "unconnected-(U$25-R0-PadRO)") (class "Default")
      (node (ref "U$25") (pin "RO") (pinfunction "R0_RO") (pintype "bidirectional"))
    )
    (net (code "192") (name "unconnected-(U$26-PadDI)") (class "Default")
      (node (ref "U$26") (pin "DI") (pinfunction "DI_DI") (pintype "bidirectional"))
    )
    (net (code "193") (name "unconnected-(U$26-PadVCC)") (class "Default")
      (node (ref "U$26") (pin "VCC") (pinfunction "VCC_VCC") (pintype "bidirectional"))
    )
    (net (code "194") (name "unconnected-(U$26-R0-PadRO)") (class "Default")
      (node (ref "U$26") (pin "RO") (pinfunction "R0_RO") (pintype "bidirectional"))
    )
    (net (code "195") (name "unconnected-(U$27-PadDI)") (class "Default")
      (node (ref "U$27") (pin "DI") (pinfunction "DI_DI") (pintype "bidirectional"))
    )
    (net (code "196") (name "unconnected-(U$27-PadVCC)") (class "Default")
      (node (ref "U$27") (pin "VCC") (pinfunction "VCC_VCC") (pintype "bidirectional"))
    )
    (net (code "197") (name "unconnected-(U$27-R0-PadRO)") (class "Default")
      (node (ref "U$27") (pin "RO") (pinfunction "R0_RO") (pintype "bidirectional"))
    )
    (net (code "198") (name "unconnected-(U$28-PadDI)") (class "Default")
      (node (ref "U$28") (pin "DI") (pinfunction "DI_DI") (pintype "bidirectional"))
    )
    (net (code "199") (name "unconnected-(U$28-PadVCC)") (class "Default")
      (node (ref "U$28") (pin "VCC") (pinfunction "VCC_VCC") (pintype "bidirectional"))
    )
    (net (code "200") (name "unconnected-(U$28-R0-PadRO)") (class "Default")
      (node (ref "U$28") (pin "RO") (pinfunction "R0_RO") (pintype "bidirectional"))
    )
    (net (code "201") (name "unconnected-(U$29-PadDI)") (class "Default")
      (node (ref "U$29") (pin "DI") (pinfunction "DI_DI") (pintype "bidirectional"))
    )
    (net (code "202") (name "unconnected-(U$29-PadVCC)") (class "Default")
      (node (ref "U$29") (pin "VCC") (pinfunction "VCC_VCC") (pintype "bidirectional"))
    )
    (net (code "203") (name "unconnected-(U$29-R0-PadRO)") (class "Default")
      (node (ref "U$29") (pin "RO") (pinfunction "R0_RO") (pintype "bidirectional"))
    )
    (net (code "204") (name "unconnected-(U$30-PadDI)") (class "Default")
      (node (ref "U$30") (pin "DI") (pinfunction "DI_DI") (pintype "bidirectional"))
    )
    (net (code "205") (name "unconnected-(U$30-PadVCC)") (class "Default")
      (node (ref "U$30") (pin "VCC") (pinfunction "VCC_VCC") (pintype "bidirectional"))
    )
    (net (code "206") (name "unconnected-(U$30-R0-PadRO)") (class "Default")
      (node (ref "U$30") (pin "RO") (pinfunction "R0_RO") (pintype "bidirectional"))
    )
    (net (code "207") (name "unconnected-(U$31-PadDI)") (class "Default")
      (node (ref "U$31") (pin "DI") (pinfunction "DI_DI") (pintype "bidirectional"))
    )
    (net (code "208") (name "unconnected-(U$31-PadVCC)") (class "Default")
      (node (ref "U$31") (pin "VCC") (pinfunction "VCC_VCC") (pintype "bidirectional"))
    )
    (net (code "209") (name "unconnected-(U$31-R0-PadRO)") (class "Default")
      (node (ref "U$31") (pin "RO") (pinfunction "R0_RO") (pintype "bidirectional"))
    )
    (net (code "210") (name "unconnected-(U$32-PadDI)") (class "Default")
      (node (ref "U$32") (pin "DI") (pinfunction "DI_DI") (pintype "bidirectional"))
    )
    (net (code "211") (name "unconnected-(U$32-PadVCC)") (class "Default")
      (node (ref "U$32") (pin "VCC") (pinfunction "VCC_VCC") (pintype "bidirectional"))
    )
    (net (code "212") (name "unconnected-(U$32-R0-PadRO)") (class "Default")
      (node (ref "U$32") (pin "RO") (pinfunction "R0_RO") (pintype "bidirectional"))
    )
    (net (code "213") (name "unconnected-(U$33-PadDI)") (class "Default")
      (node (ref "U$33") (pin "DI") (pinfunction "DI_DI") (pintype "bidirectional"))
    )
    (net (code "214") (name "unconnected-(U$33-PadVCC)") (class "Default")
      (node (ref "U$33") (pin "VCC") (pinfunction "VCC_VCC") (pintype "bidirectional"))
    )
    (net (code "215") (name "unconnected-(U$33-R0-PadRO)") (class "Default")
      (node (ref "U$33") (pin "RO") (pinfunction "R0_RO") (pintype "bidirectional"))
    )
    (net (code "216") (name "unconnected-(U$34-PadDI)") (class "Default")
      (node (ref "U$34") (pin "DI") (pinfunction "DI_DI") (pintype "bidirectional"))
    )
    (net (code "217") (name "unconnected-(U$34-PadVCC)") (class "Default")
      (node (ref "U$34") (pin "VCC") (pinfunction "VCC_VCC") (pintype "bidirectional"))
    )
    (net (code "218") (name "unconnected-(U$34-R0-PadRO)") (class "Default")
      (node (ref "U$34") (pin "RO") (pinfunction "R0_RO") (pintype "bidirectional"))
    )
    (net (code "219") (name "unconnected-(U$35-PadDI)") (class "Default")
      (node (ref "U$35") (pin "DI") (pinfunction "DI_DI") (pintype "bidirectional"))
    )
    (net (code "220") (name "unconnected-(U$35-PadVCC)") (class "Default")
      (node (ref "U$35") (pin "VCC") (pinfunction "VCC_VCC") (pintype "bidirectional"))
    )
    (net (code "221") (name "unconnected-(U$35-R0-PadRO)") (class "Default")
      (node (ref "U$35") (pin "RO") (pinfunction "R0_RO") (pintype "bidirectional"))
    )
    (net (code "222") (name "unconnected-(U$36-Pad49)") (class "Default")
      (node (ref "U$36") (pin "49") (pinfunction "49_49") (pintype "bidirectional"))
    )
    (net (code "223") (name "unconnected-(U$36-Pad50)") (class "Default")
      (node (ref "U$36") (pin "50") (pinfunction "50_50") (pintype "bidirectional"))
    )
    (net (code "224") (name "unconnected-(U$36-Pad51)") (class "Default")
      (node (ref "U$36") (pin "51") (pinfunction "51_51") (pintype "bidirectional"))
    )
    (net (code "225") (name "unconnected-(U$36-Pad52)") (class "Default")
      (node (ref "U$36") (pin "52") (pinfunction "52_52") (pintype "bidirectional"))
    )
    (net (code "226") (name "unconnected-(U$36-Pad53)") (class "Default")
      (node (ref "U$36") (pin "53") (pinfunction "53_53") (pintype "bidirectional"))
    )
    (net (code "227") (name "unconnected-(U$36-Pad54)") (class "Default")
      (node (ref "U$36") (pin "54") (pinfunction "54_54") (pintype "bidirectional"))
    )
    (net (code "228") (name "unconnected-(U$36-Pad55)") (class "Default")
      (node (ref "U$36") (pin "55") (pinfunction "55_55") (pintype "bidirectional"))
    )
    (net (code "229") (name "unconnected-(U$36-Pad56)") (class "Default")
      (node (ref "U$36") (pin "56") (pinfunction "56_56") (pintype "bidirectional"))
    )
    (net (code "230") (name "unconnected-(U$36-Pad57)") (class "Default")
      (node (ref "U$36") (pin "57") (pinfunction "57_57") (pintype "bidirectional"))
    )
    (net (code "231") (name "unconnected-(U$36-Pad58)") (class "Default")
      (node (ref "U$36") (pin "58") (pinfunction "58_58") (pintype "bidirectional"))
    )
    (net (code "232") (name "unconnected-(U$36-Pad59)") (class "Default")
      (node (ref "U$36") (pin "59") (pinfunction "59_59") (pintype "bidirectional"))
    )
    (net (code "233") (name "unconnected-(U$36-Pad60)") (class "Default")
      (node (ref "U$36") (pin "60") (pinfunction "60_60") (pintype "bidirectional"))
    )
    (net (code "234") (name "unconnected-(U$36-Pad61)") (class "Default")
      (node (ref "U$36") (pin "61") (pinfunction "61_61") (pintype "bidirectional"))
    )
    (net (code "235") (name "unconnected-(U$36-Pad62)") (class "Default")
      (node (ref "U$36") (pin "62") (pinfunction "62_62") (pintype "bidirectional"))
    )
    (net (code "236") (name "unconnected-(U$36-Pad63)") (class "Default")
      (node (ref "U$36") (pin "63") (pinfunction "63_63") (pintype "bidirectional"))
    )
    (net (code "237") (name "unconnected-(U$36-Pad64)") (class "Default")
      (node (ref "U$36") (pin "64") (pinfunction "64_64") (pintype "bidirectional"))
    )
    (net (code "238") (name "unconnected-(U$36-Pad65)") (class "Default")
      (node (ref "U$36") (pin "65") (pinfunction "65_65") (pintype "bidirectional"))
    )
    (net (code "239") (name "unconnected-(U$36-Pad66)") (class "Default")
      (node (ref "U$36") (pin "66") (pinfunction "66_66") (pintype "bidirectional"))
    )
    (net (code "240") (name "unconnected-(U$36-Pad67)") (class "Default")
      (node (ref "U$36") (pin "67") (pinfunction "67_67") (pintype "bidirectional"))
    )
    (net (code "241") (name "unconnected-(U$36-Pad68)") (class "Default")
      (node (ref "U$36") (pin "68") (pinfunction "68_68") (pintype "bidirectional"))
    )
    (net (code "242") (name "unconnected-(U1A-ADC0_DM1-Pad15)") (class "Default")
      (node (ref "U1") (pin "15") (pinfunction "ADC0_DM1_15") (pintype "passive"))
    )
    (net (code "243") (name "unconnected-(U1A-ADC0_DP1-Pad14)") (class "Default")
      (node (ref "U1") (pin "14") (pinfunction "ADC0_DP1_14") (pintype "passive"))
    )
    (net (code "244") (name "unconnected-(U1A-ADC1_DM1-Pad17)") (class "Default")
      (node (ref "U1") (pin "17") (pinfunction "ADC1_DM1_17") (pintype "passive"))
    )
    (net (code "245") (name "unconnected-(U1A-ADC1_DP1-Pad16)") (class "Default")
      (node (ref "U1") (pin "16") (pinfunction "ADC1_DP1_16") (pintype "passive"))
    )
    (net (code "246") (name "unconnected-(U1A-PGA0_DM{slash}ADC0_DM0{slash}ADC1_DM3-Pad19)") (class "Default")
      (node (ref "U1") (pin "19") (pinfunction "PGA0_DM/ADC0_DM0/ADC1_DM3_19") (pintype "passive"))
    )
    (net (code "247") (name "unconnected-(U1A-PGA0_DP{slash}ADC0_DP0{slash}ADC1_DP3-Pad18)") (class "Default")
      (node (ref "U1") (pin "18") (pinfunction "PGA0_DP/ADC0_DP0/ADC1_DP3_18") (pintype "passive"))
    )
    (net (code "248") (name "unconnected-(U1A-PGA1_DP{slash}ADC1_DP0{slash}ADC0_DP3-Pad20)") (class "Default")
      (node (ref "U1") (pin "20") (pinfunction "PGA1_DP/ADC1_DP0/ADC0_DP3_20") (pintype "passive"))
    )
    (net (code "249") (name "unconnected-(U1A-PTA4-Pad38)") (class "Default")
      (node (ref "U1") (pin "38") (pinfunction "PTA4_38") (pintype "bidirectional"))
    )
    (net (code "250") (name "unconnected-(U1A-PTA12-Pad42)") (class "Default")
      (node (ref "U1") (pin "42") (pinfunction "PTA12_42") (pintype "bidirectional"))
    )
    (net (code "251") (name "unconnected-(U1A-PTA13-Pad43)") (class "Default")
      (node (ref "U1") (pin "43") (pinfunction "PTA13_43") (pintype "bidirectional"))
    )
    (net (code "252") (name "unconnected-(U1A-PTA14-Pad44)") (class "Default")
      (node (ref "U1") (pin "44") (pinfunction "PTA14_44") (pintype "bidirectional"))
    )
    (net (code "253") (name "unconnected-(U1A-PTA15-Pad45)") (class "Default")
      (node (ref "U1") (pin "45") (pinfunction "PTA15_45") (pintype "bidirectional"))
    )
    (net (code "254") (name "unconnected-(U1A-PTA16-Pad46)") (class "Default")
      (node (ref "U1") (pin "46") (pinfunction "PTA16_46") (pintype "bidirectional"))
    )
    (net (code "255") (name "unconnected-(U1A-PTA17-Pad47)") (class "Default")
      (node (ref "U1") (pin "47") (pinfunction "PTA17_47") (pintype "bidirectional"))
    )
    (net (code "256") (name "unconnected-(U1A-PTB0-Pad53)") (class "Default")
      (node (ref "U1") (pin "53") (pinfunction "PTB0_53") (pintype "bidirectional"))
    )
    (net (code "257") (name "unconnected-(U1A-PTB1-Pad54)") (class "Default")
      (node (ref "U1") (pin "54") (pinfunction "PTB1_54") (pintype "bidirectional"))
    )
    (net (code "258") (name "unconnected-(U1A-PTB2-Pad55)") (class "Default")
      (node (ref "U1") (pin "55") (pinfunction "PTB2_55") (pintype "bidirectional"))
    )
    (net (code "259") (name "unconnected-(U1A-PTB3-Pad56)") (class "Default")
      (node (ref "U1") (pin "56") (pinfunction "PTB3_56") (pintype "bidirectional"))
    )
    (net (code "260") (name "unconnected-(U1A-PTB9-Pad57)") (class "Default")
      (node (ref "U1") (pin "57") (pinfunction "PTB9_57") (pintype "bidirectional"))
    )
    (net (code "261") (name "unconnected-(U1A-PTB10-Pad58)") (class "Default")
      (node (ref "U1") (pin "58") (pinfunction "PTB10_58") (pintype "bidirectional"))
    )
    (net (code "262") (name "unconnected-(U1A-PTB11-Pad59)") (class "Default")
      (node (ref "U1") (pin "59") (pinfunction "PTB11_59") (pintype "bidirectional"))
    )
    (net (code "263") (name "unconnected-(U1A-PTE0-Pad1)") (class "Default")
      (node (ref "U1") (pin "1") (pinfunction "PTE0_1") (pintype "bidirectional"))
    )
    (net (code "264") (name "unconnected-(U1A-PTE1-Pad2)") (class "Default")
      (node (ref "U1") (pin "2") (pinfunction "PTE1_2") (pintype "bidirectional"))
    )
    (net (code "265") (name "unconnected-(U1A-PTE2-Pad3)") (class "Default")
      (node (ref "U1") (pin "3") (pinfunction "PTE2_3") (pintype "bidirectional"))
    )
    (net (code "266") (name "unconnected-(U1A-PTE3-Pad4)") (class "Default")
      (node (ref "U1") (pin "4") (pinfunction "PTE3_4") (pintype "bidirectional"))
    )
    (net (code "267") (name "unconnected-(U1A-PTE4-Pad5)") (class "Default")
      (node (ref "U1") (pin "5") (pinfunction "PTE4_5") (pintype "bidirectional"))
    )
    (net (code "268") (name "unconnected-(U1A-PTE5-Pad6)") (class "Default")
      (node (ref "U1") (pin "6") (pinfunction "PTE5_6") (pintype "bidirectional"))
    )
    (net (code "269") (name "unconnected-(U1A-PTE6-Pad7)") (class "Default")
      (node (ref "U1") (pin "7") (pinfunction "PTE6_7") (pintype "bidirectional"))
    )
    (net (code "270") (name "unconnected-(U1A-PTE16-Pad10)") (class "Default")
      (node (ref "U1") (pin "10") (pinfunction "PTE16_10") (pintype "bidirectional"))
    )
    (net (code "271") (name "unconnected-(U1A-PTE17-Pad11)") (class "Default")
      (node (ref "U1") (pin "11") (pinfunction "PTE17_11") (pintype "bidirectional"))
    )
    (net (code "272") (name "unconnected-(U1A-PTE18-Pad12)") (class "Default")
      (node (ref "U1") (pin "12") (pinfunction "PTE18_12") (pintype "bidirectional"))
    )
    (net (code "273") (name "unconnected-(U1A-PTE19-Pad13)") (class "Default")
      (node (ref "U1") (pin "13") (pinfunction "PTE19_13") (pintype "bidirectional"))
    )
    (net (code "274") (name "unconnected-(U1A-PTE24-Pad31)") (class "Default")
      (node (ref "U1") (pin "31") (pinfunction "PTE24_31") (pintype "bidirectional"))
    )
    (net (code "275") (name "unconnected-(U1A-PTE25-Pad32)") (class "Default")
      (node (ref "U1") (pin "32") (pinfunction "PTE25_32") (pintype "bidirectional"))
    )
    (net (code "276") (name "unconnected-(U1A-PTE26-Pad33)") (class "Default")
      (node (ref "U1") (pin "33") (pinfunction "PTE26_33") (pintype "bidirectional"))
    )
    (net (code "277") (name "unconnected-(U1B-DAC0_OUT{slash}CMP1_IN3{slash}ADC0_SE23-Pad27)") (class "Default")
      (node (ref "U1") (pin "27") (pinfunction "DAC0_OUT/CMP1_IN3/ADC0_SE23_27") (pintype "passive"))
    )
    (net (code "278") (name "unconnected-(U1B-EXTAL32-Pad29)") (class "Default")
      (node (ref "U1") (pin "29") (pinfunction "EXTAL32_29") (pintype "passive"))
    )
    (net (code "279") (name "unconnected-(U1B-PGA1_DM{slash}ADC1_DM0{slash}ADC0_DM3-Pad21)") (class "Default")
      (node (ref "U1") (pin "21") (pinfunction "PGA1_DM/ADC1_DM0/ADC0_DM3_21") (pintype "passive"))
    )
    (net (code "280") (name "unconnected-(U1B-PTB16-Pad62)") (class "Default")
      (node (ref "U1") (pin "62") (pinfunction "PTB16_62") (pintype "bidirectional"))
    )
    (net (code "281") (name "unconnected-(U1B-PTB17-Pad63)") (class "Default")
      (node (ref "U1") (pin "63") (pinfunction "PTB17_63") (pintype "bidirectional"))
    )
    (net (code "282") (name "unconnected-(U1B-PTB18-Pad64)") (class "Default")
      (node (ref "U1") (pin "64") (pinfunction "PTB18_64") (pintype "bidirectional"))
    )
    (net (code "283") (name "unconnected-(U1B-PTB19-Pad65)") (class "Default")
      (node (ref "U1") (pin "65") (pinfunction "PTB19_65") (pintype "bidirectional"))
    )
    (net (code "284") (name "unconnected-(U1B-PTB20-Pad66)") (class "Default")
      (node (ref "U1") (pin "66") (pinfunction "PTB20_66") (pintype "bidirectional"))
    )
    (net (code "285") (name "unconnected-(U1B-PTB21-Pad67)") (class "Default")
      (node (ref "U1") (pin "67") (pinfunction "PTB21_67") (pintype "bidirectional"))
    )
    (net (code "286") (name "unconnected-(U1B-PTB22-Pad68)") (class "Default")
      (node (ref "U1") (pin "68") (pinfunction "PTB22_68") (pintype "bidirectional"))
    )
    (net (code "287") (name "unconnected-(U1B-PTB23-Pad69)") (class "Default")
      (node (ref "U1") (pin "69") (pinfunction "PTB23_69") (pintype "bidirectional"))
    )
    (net (code "288") (name "unconnected-(U1B-PTC0-Pad70)") (class "Default")
      (node (ref "U1") (pin "70") (pinfunction "PTC0_70") (pintype "bidirectional"))
    )
    (net (code "289") (name "unconnected-(U1B-PTC1-Pad71)") (class "Default")
      (node (ref "U1") (pin "71") (pinfunction "PTC1_71") (pintype "bidirectional"))
    )
    (net (code "290") (name "unconnected-(U1B-PTC2-Pad72)") (class "Default")
      (node (ref "U1") (pin "72") (pinfunction "PTC2_72") (pintype "bidirectional"))
    )
    (net (code "291") (name "unconnected-(U1B-PTC3-Pad73)") (class "Default")
      (node (ref "U1") (pin "73") (pinfunction "PTC3_73") (pintype "bidirectional"))
    )
    (net (code "292") (name "unconnected-(U1B-PTC4-Pad76)") (class "Default")
      (node (ref "U1") (pin "76") (pinfunction "PTC4_76") (pintype "bidirectional"))
    )
    (net (code "293") (name "unconnected-(U1B-PTC5-Pad77)") (class "Default")
      (node (ref "U1") (pin "77") (pinfunction "PTC5_77") (pintype "bidirectional"))
    )
    (net (code "294") (name "unconnected-(U1B-PTC6-Pad78)") (class "Default")
      (node (ref "U1") (pin "78") (pinfunction "PTC6_78") (pintype "bidirectional"))
    )
    (net (code "295") (name "unconnected-(U1B-PTC7-Pad79)") (class "Default")
      (node (ref "U1") (pin "79") (pinfunction "PTC7_79") (pintype "bidirectional"))
    )
    (net (code "296") (name "unconnected-(U1B-PTC8-Pad80)") (class "Default")
      (node (ref "U1") (pin "80") (pinfunction "PTC8_80") (pintype "bidirectional"))
    )
    (net (code "297") (name "unconnected-(U1B-PTC9-Pad81)") (class "Default")
      (node (ref "U1") (pin "81") (pinfunction "PTC9_81") (pintype "bidirectional"))
    )
    (net (code "298") (name "unconnected-(U1B-PTC10-Pad82)") (class "Default")
      (node (ref "U1") (pin "82") (pinfunction "PTC10_82") (pintype "bidirectional"))
    )
    (net (code "299") (name "unconnected-(U1B-PTC11-Pad83)") (class "Default")
      (node (ref "U1") (pin "83") (pinfunction "PTC11_83") (pintype "bidirectional"))
    )
    (net (code "300") (name "unconnected-(U1B-PTC12-Pad84)") (class "Default")
      (node (ref "U1") (pin "84") (pinfunction "PTC12_84") (pintype "bidirectional"))
    )
    (net (code "301") (name "unconnected-(U1B-PTC13-Pad85)") (class "Default")
      (node (ref "U1") (pin "85") (pinfunction "PTC13_85") (pintype "bidirectional"))
    )
    (net (code "302") (name "unconnected-(U1B-PTC14-Pad86)") (class "Default")
      (node (ref "U1") (pin "86") (pinfunction "PTC14_86") (pintype "bidirectional"))
    )
    (net (code "303") (name "unconnected-(U1B-PTC15-Pad87)") (class "Default")
      (node (ref "U1") (pin "87") (pinfunction "PTC15_87") (pintype "bidirectional"))
    )
    (net (code "304") (name "unconnected-(U1B-PTC16-Pad90)") (class "Default")
      (node (ref "U1") (pin "90") (pinfunction "PTC16_90") (pintype "bidirectional"))
    )
    (net (code "305") (name "unconnected-(U1B-PTC17-Pad91)") (class "Default")
      (node (ref "U1") (pin "91") (pinfunction "PTC17_91") (pintype "bidirectional"))
    )
    (net (code "306") (name "unconnected-(U1B-PTC18-Pad92)") (class "Default")
      (node (ref "U1") (pin "92") (pinfunction "PTC18_92") (pintype "bidirectional"))
    )
    (net (code "307") (name "unconnected-(U1B-PTD0-Pad93)") (class "Default")
      (node (ref "U1") (pin "93") (pinfunction "PTD0_93") (pintype "bidirectional"))
    )
    (net (code "308") (name "unconnected-(U1B-PTD1-Pad94)") (class "Default")
      (node (ref "U1") (pin "94") (pinfunction "PTD1_94") (pintype "bidirectional"))
    )
    (net (code "309") (name "unconnected-(U1B-PTD2-Pad95)") (class "Default")
      (node (ref "U1") (pin "95") (pinfunction "PTD2_95") (pintype "bidirectional"))
    )
    (net (code "310") (name "unconnected-(U1B-PTD3-Pad96)") (class "Default")
      (node (ref "U1") (pin "96") (pinfunction "PTD3_96") (pintype "bidirectional"))
    )
    (net (code "311") (name "unconnected-(U1B-PTD4-Pad97)") (class "Default")
      (node (ref "U1") (pin "97") (pinfunction "PTD4_97") (pintype "bidirectional"))
    )
    (net (code "312") (name "unconnected-(U1B-PTD5-Pad98)") (class "Default")
      (node (ref "U1") (pin "98") (pinfunction "PTD5_98") (pintype "bidirectional"))
    )
    (net (code "313") (name "unconnected-(U1B-PTD6-Pad99)") (class "Default")
      (node (ref "U1") (pin "99") (pinfunction "PTD6_99") (pintype "bidirectional"))
    )
    (net (code "314") (name "unconnected-(U1B-PTD7-Pad100)") (class "Default")
      (node (ref "U1") (pin "100") (pinfunction "PTD7_100") (pintype "bidirectional"))
    )
    (net (code "315") (name "unconnected-(U1B-VREF_OUT{slash}CMP1_IN5{slash}CMP0_IN5{slash}ADC1_SE18-Pad26)") (class "Default")
      (node (ref "U1") (pin "26") (pinfunction "VREF_OUT/CMP1_IN5/CMP0_IN5/ADC1_SE18_26") (pintype "passive"))
    )
    (net (code "316") (name "unconnected-(U1B-XTAL32-Pad28)") (class "Default")
      (node (ref "U1") (pin "28") (pinfunction "XTAL32_28") (pintype "passive"))
    )
    (net (code "317") (name "unconnected-(U2-AVCC-Pad32)") (class "Default")
      (node (ref "U2") (pin "32") (pinfunction "AVCC_32") (pintype "bidirectional"))
    )
    (net (code "318") (name "unconnected-(U2-D+-Pad29)") (class "Default")
      (node (ref "U2") (pin "29") (pinfunction "D+_29") (pintype "bidirectional"))
    )
    (net (code "319") (name "unconnected-(U2-D--Pad30)") (class "Default")
      (node (ref "U2") (pin "30") (pinfunction "D-_30") (pintype "bidirectional"))
    )
    (net (code "320") (name "unconnected-(U2-GND-Pad3)") (class "Default")
      (node (ref "U2") (pin "3") (pinfunction "GND_3") (pintype "bidirectional"))
    )
    (net (code "321") (name "unconnected-(U2-PB0-Pad14)") (class "Default")
      (node (ref "U2") (pin "14") (pinfunction "PB0_14") (pintype "bidirectional"))
    )
    (net (code "322") (name "unconnected-(U2-PB1(SCK)-Pad15)") (class "Default")
      (node (ref "U2") (pin "15") (pinfunction "PB1(SCK)_15") (pintype "bidirectional"))
    )
    (net (code "323") (name "unconnected-(U2-PB2(MOSI)-Pad16)") (class "Default")
      (node (ref "U2") (pin "16") (pinfunction "PB2(MOSI)_16") (pintype "bidirectional"))
    )
    (net (code "324") (name "unconnected-(U2-PB3(MISO)-Pad17)") (class "Default")
      (node (ref "U2") (pin "17") (pinfunction "PB3(MISO)_17") (pintype "bidirectional"))
    )
    (net (code "325") (name "unconnected-(U2-PB4-Pad18)") (class "Default")
      (node (ref "U2") (pin "18") (pinfunction "PB4_18") (pintype "bidirectional"))
    )
    (net (code "326") (name "unconnected-(U2-PB5-Pad19)") (class "Default")
      (node (ref "U2") (pin "19") (pinfunction "PB5_19") (pintype "bidirectional"))
    )
    (net (code "327") (name "unconnected-(U2-PB6-Pad20)") (class "Default")
      (node (ref "U2") (pin "20") (pinfunction "PB6_20") (pintype "bidirectional"))
    )
    (net (code "328") (name "unconnected-(U2-PB7-Pad21)") (class "Default")
      (node (ref "U2") (pin "21") (pinfunction "PB7_21") (pintype "bidirectional"))
    )
    (net (code "329") (name "unconnected-(U2-PC2-Pad5)") (class "Default")
      (node (ref "U2") (pin "5") (pinfunction "PC2_5") (pintype "bidirectional"))
    )
    (net (code "330") (name "unconnected-(U2-PC4-Pad26)") (class "Default")
      (node (ref "U2") (pin "26") (pinfunction "PC4_26") (pintype "bidirectional"))
    )
    (net (code "331") (name "unconnected-(U2-PC5-Pad25)") (class "Default")
      (node (ref "U2") (pin "25") (pinfunction "PC5_25") (pintype "bidirectional"))
    )
    (net (code "332") (name "unconnected-(U2-PC6-Pad23)") (class "Default")
      (node (ref "U2") (pin "23") (pinfunction "PC6_23") (pintype "bidirectional"))
    )
    (net (code "333") (name "unconnected-(U2-PC7-Pad22)") (class "Default")
      (node (ref "U2") (pin "22") (pinfunction "PC7_22") (pintype "bidirectional"))
    )
    (net (code "334") (name "unconnected-(U2-PD0-Pad6)") (class "Default")
      (node (ref "U2") (pin "6") (pinfunction "PD0_6") (pintype "bidirectional"))
    )
    (net (code "335") (name "unconnected-(U2-PD1-Pad7)") (class "Default")
      (node (ref "U2") (pin "7") (pinfunction "PD1_7") (pintype "bidirectional"))
    )
    (net (code "336") (name "unconnected-(U2-PD2(RX)-Pad8)") (class "Default")
      (node (ref "U2") (pin "8") (pinfunction "PD2(RX)_8") (pintype "bidirectional"))
    )
    (net (code "337") (name "unconnected-(U2-PD3(TX)-Pad9)") (class "Default")
      (node (ref "U2") (pin "9") (pinfunction "PD3(TX)_9") (pintype "bidirectional"))
    )
    (net (code "338") (name "unconnected-(U2-PD4-Pad10)") (class "Default")
      (node (ref "U2") (pin "10") (pinfunction "PD4_10") (pintype "bidirectional"))
    )
    (net (code "339") (name "unconnected-(U2-PD5-Pad11)") (class "Default")
      (node (ref "U2") (pin "11") (pinfunction "PD5_11") (pintype "bidirectional"))
    )
    (net (code "340") (name "unconnected-(U2-PD6(RTS)-Pad12)") (class "Default")
      (node (ref "U2") (pin "12") (pinfunction "PD6(RTS)_12") (pintype "bidirectional"))
    )
    (net (code "341") (name "unconnected-(U2-PD7(CTS)-Pad13)") (class "Default")
      (node (ref "U2") (pin "13") (pinfunction "PD7(CTS)_13") (pintype "bidirectional"))
    )
    (net (code "342") (name "unconnected-(U2-RESET{slash}PC1-Pad24)") (class "Default")
      (node (ref "U2") (pin "24") (pinfunction "RESET/PC1_24") (pintype "bidirectional"))
    )
    (net (code "343") (name "unconnected-(U2-UCAP-Pad27)") (class "Default")
      (node (ref "U2") (pin "27") (pinfunction "UCAP_27") (pintype "bidirectional"))
    )
    (net (code "344") (name "unconnected-(U2-UGND-Pad28)") (class "Default")
      (node (ref "U2") (pin "28") (pinfunction "UGND_28") (pintype "bidirectional"))
    )
    (net (code "345") (name "unconnected-(U2-UVCC-Pad31)") (class "Default")
      (node (ref "U2") (pin "31") (pinfunction "UVCC_31") (pintype "bidirectional"))
    )
    (net (code "346") (name "unconnected-(U2-VCC-Pad4)") (class "Default")
      (node (ref "U2") (pin "4") (pinfunction "VCC_4") (pintype "bidirectional"))
    )
    (net (code "347") (name "unconnected-(U2-XTAL1-Pad1)") (class "Default")
      (node (ref "U2") (pin "1") (pinfunction "XTAL1_1") (pintype "bidirectional"))
    )
    (net (code "348") (name "unconnected-(U2-XTAL2{slash}PC0-Pad2)") (class "Default")
      (node (ref "U2") (pin "2") (pinfunction "XTAL2/PC0_2") (pintype "bidirectional"))
    )
    (net (code "349") (name "unconnected-(U7-1PPS-PadP$13)") (class "Default")
      (node (ref "U7") (pin "P$13") (pinfunction "1PPS_P$13") (pintype "bidirectional"))
    )
    (net (code "350") (name "unconnected-(U7-3D-FIX-PadP$5)") (class "Default")
      (node (ref "U7") (pin "P$5") (pinfunction "3D-FIX_P$5") (pintype "bidirectional"))
    )
    (net (code "351") (name "unconnected-(U7-EX_ANT-PadP$11)") (class "Default")
      (node (ref "U7") (pin "P$11") (pinfunction "EX_ANT_P$11") (pintype "bidirectional"))
    )
    (net (code "352") (name "unconnected-(U7-NC-PadP$6)") (class "Default")
      (node (ref "U7") (pin "P$6") (pinfunction "NC_P$6") (pintype "bidirectional"))
    )
    (net (code "353") (name "unconnected-(U7-NC-PadP$7)") (class "Default")
      (node (ref "U7") (pin "P$7") (pinfunction "NC_P$7") (pintype "bidirectional"))
    )
    (net (code "354") (name "unconnected-(U7-NC-PadP$15)") (class "Default")
      (node (ref "U7") (pin "P$15") (pinfunction "NC_P$15") (pintype "bidirectional"))
    )
    (net (code "355") (name "unconnected-(U7-NC-PadP$16)") (class "Default")
      (node (ref "U7") (pin "P$16") (pinfunction "NC_P$16") (pintype "bidirectional"))
    )
    (net (code "356") (name "unconnected-(U7-NC-PadP$17)") (class "Default")
      (node (ref "U7") (pin "P$17") (pinfunction "NC_P$17") (pintype "bidirectional"))
    )
    (net (code "357") (name "unconnected-(U7-NC-PadP$18)") (class "Default")
      (node (ref "U7") (pin "P$18") (pinfunction "NC_P$18") (pintype "bidirectional"))
    )
    (net (code "358") (name "unconnected-(U7-NC-PadP$20)") (class "Default")
      (node (ref "U7") (pin "P$20") (pinfunction "NC_P$20") (pintype "bidirectional"))
    )
    (net (code "359") (name "unconnected-(U7-NRESET-PadP$2)") (class "Default")
      (node (ref "U7") (pin "P$2") (pinfunction "NRESET_P$2") (pintype "bidirectional"))
    )
    (net (code "360") (name "unconnected-(U7-RTCM-PadP$14)") (class "Default")
      (node (ref "U7") (pin "P$14") (pinfunction "RTCM_P$14") (pintype "bidirectional"))
    )
    (net (code "361") (name "unconnected-(U7-RX-PadP$10)") (class "Default")
      (node (ref "U7") (pin "P$10") (pinfunction "RX_P$10") (pintype "bidirectional"))
    )
    (net (code "362") (name "unconnected-(U7-TX-PadP$9)") (class "Default")
      (node (ref "U7") (pin "P$9") (pinfunction "TX_P$9") (pintype "bidirectional"))
    )
    (net (code "363") (name "unconnected-(U7-VBACKUP-PadP$4)") (class "Default")
      (node (ref "U7") (pin "P$4") (pinfunction "VBACKUP_P$4") (pintype "bidirectional"))
    )
    (net (code "364") (name "unconnected-(U7-VCC-PadP$1)") (class "Default")
      (node (ref "U7") (pin "P$1") (pinfunction "VCC_P$1") (pintype "bidirectional"))
    )
    (net (code "365") (name "unconnected-(U8-AD0-Pad9)") (class "Default")
      (node (ref "U8") (pin "9") (pinfunction "AD0_9") (pintype "bidirectional"))
    )
    (net (code "366") (name "unconnected-(U8-CLKIN-Pad1)") (class "Default")
      (node (ref "U8") (pin "1") (pinfunction "CLKIN_1") (pintype "bidirectional"))
    )
    (net (code "367") (name "unconnected-(U8-CLKOUT-Pad22)") (class "Default")
      (node (ref "U8") (pin "22") (pinfunction "CLKOUT_22") (pintype "bidirectional"))
    )
    (net (code "368") (name "unconnected-(U8-CPOUT-Pad20)") (class "Default")
      (node (ref "U8") (pin "20") (pinfunction "CPOUT_20") (pintype "bidirectional"))
    )
    (net (code "369") (name "unconnected-(U8-E_SCL-Pad7)") (class "Default")
      (node (ref "U8") (pin "7") (pinfunction "E_SCL_7") (pintype "bidirectional"))
    )
    (net (code "370") (name "unconnected-(U8-E_SDA-Pad6)") (class "Default")
      (node (ref "U8") (pin "6") (pinfunction "E_SDA_6") (pintype "bidirectional"))
    )
    (net (code "371") (name "unconnected-(U8-FSYNC-Pad11)") (class "Default")
      (node (ref "U8") (pin "11") (pinfunction "FSYNC_11") (pintype "bidirectional"))
    )
    (net (code "372") (name "unconnected-(U8-INT-Pad12)") (class "Default")
      (node (ref "U8") (pin "12") (pinfunction "INT_12") (pintype "bidirectional"))
    )
    (net (code "373") (name "unconnected-(U8-REGOUT-Pad10)") (class "Default")
      (node (ref "U8") (pin "10") (pinfunction "REGOUT_10") (pintype "bidirectional"))
    )
    (net (code "374") (name "unconnected-(U8-SCL-Pad23)") (class "Default")
      (node (ref "U8") (pin "23") (pinfunction "SCL_23") (pintype "bidirectional"))
    )
    (net (code "375") (name "unconnected-(U8-SDA-Pad24)") (class "Default")
      (node (ref "U8") (pin "24") (pinfunction "SDA_24") (pintype "bidirectional"))
    )
    (net (code "376") (name "unconnected-(U8-VDD-Pad3)") (class "Default")
      (node (ref "U8") (pin "3") (pinfunction "VDD_3") (pintype "bidirectional"))
    )
    (net (code "377") (name "unconnected-(U8-VDD-Pad13)") (class "Default")
      (node (ref "U8") (pin "13") (pinfunction "VDD_13") (pintype "bidirectional"))
    )
    (net (code "378") (name "unconnected-(U8-VLOGIC-Pad8)") (class "Default")
      (node (ref "U8") (pin "8") (pinfunction "VLOGIC_8") (pintype "bidirectional"))
    )
    (net (code "379") (name "unconnected-(U9-INT1-Pad6)") (class "Default")
      (node (ref "U9") (pin "6") (pinfunction "INT1_6") (pintype "output"))
    )
    (net (code "380") (name "unconnected-(U9-INT2-Pad5)") (class "Default")
      (node (ref "U9") (pin "5") (pinfunction "INT2_5") (pintype "output"))
    )
    (net (code "381") (name "unconnected-(U9-SCL-Pad8)") (class "Default")
      (node (ref "U9") (pin "8") (pinfunction "SCL_8") (pintype "bidirectional"))
    )
    (net (code "382") (name "unconnected-(U9-SDA-Pad7)") (class "Default")
      (node (ref "U9") (pin "7") (pinfunction "SDA_7") (pintype "bidirectional"))
    )
    (net (code "383") (name "unconnected-(U10-CAP-Pad2)") (class "Default")
      (node (ref "U10") (pin "2") (pinfunction "CAP_2") (pintype "bidirectional"))
    )
    (net (code "384") (name "unconnected-(U10-NC{slash}DOUT-Pad6)") (class "Default")
      (node (ref "U10") (pin "6") (pinfunction "NC/DOUT_6") (pintype "bidirectional"))
    )
    (net (code "385") (name "unconnected-(U10-RST{slash}CS-Pad5)") (class "Default")
      (node (ref "U10") (pin "5") (pinfunction "RST/CS_5") (pintype "bidirectional"))
    )
    (net (code "386") (name "unconnected-(U10-SCLK-Pad8)") (class "Default")
      (node (ref "U10") (pin "8") (pinfunction "SCLK_8") (pintype "bidirectional"))
    )
    (net (code "387") (name "unconnected-(U10-SDA{slash}DIN-Pad7)") (class "Default")
      (node (ref "U10") (pin "7") (pinfunction "SDA/DIN_7") (pintype "bidirectional"))
    )
    (net (code "388") (name "unconnected-(U10-SHDN-Pad4)") (class "Default")
      (node (ref "U10") (pin "4") (pinfunction "SHDN_4") (pintype "bidirectional"))
    )
    (net (code "389") (name "unconnected-(U10-VDD-Pad1)") (class "Default")
      (node (ref "U10") (pin "1") (pinfunction "VDD_1") (pintype "bidirectional"))
    )
  )
)
